# JETSON.net
KiCad netlist of a schematic drawn in Altium Designer
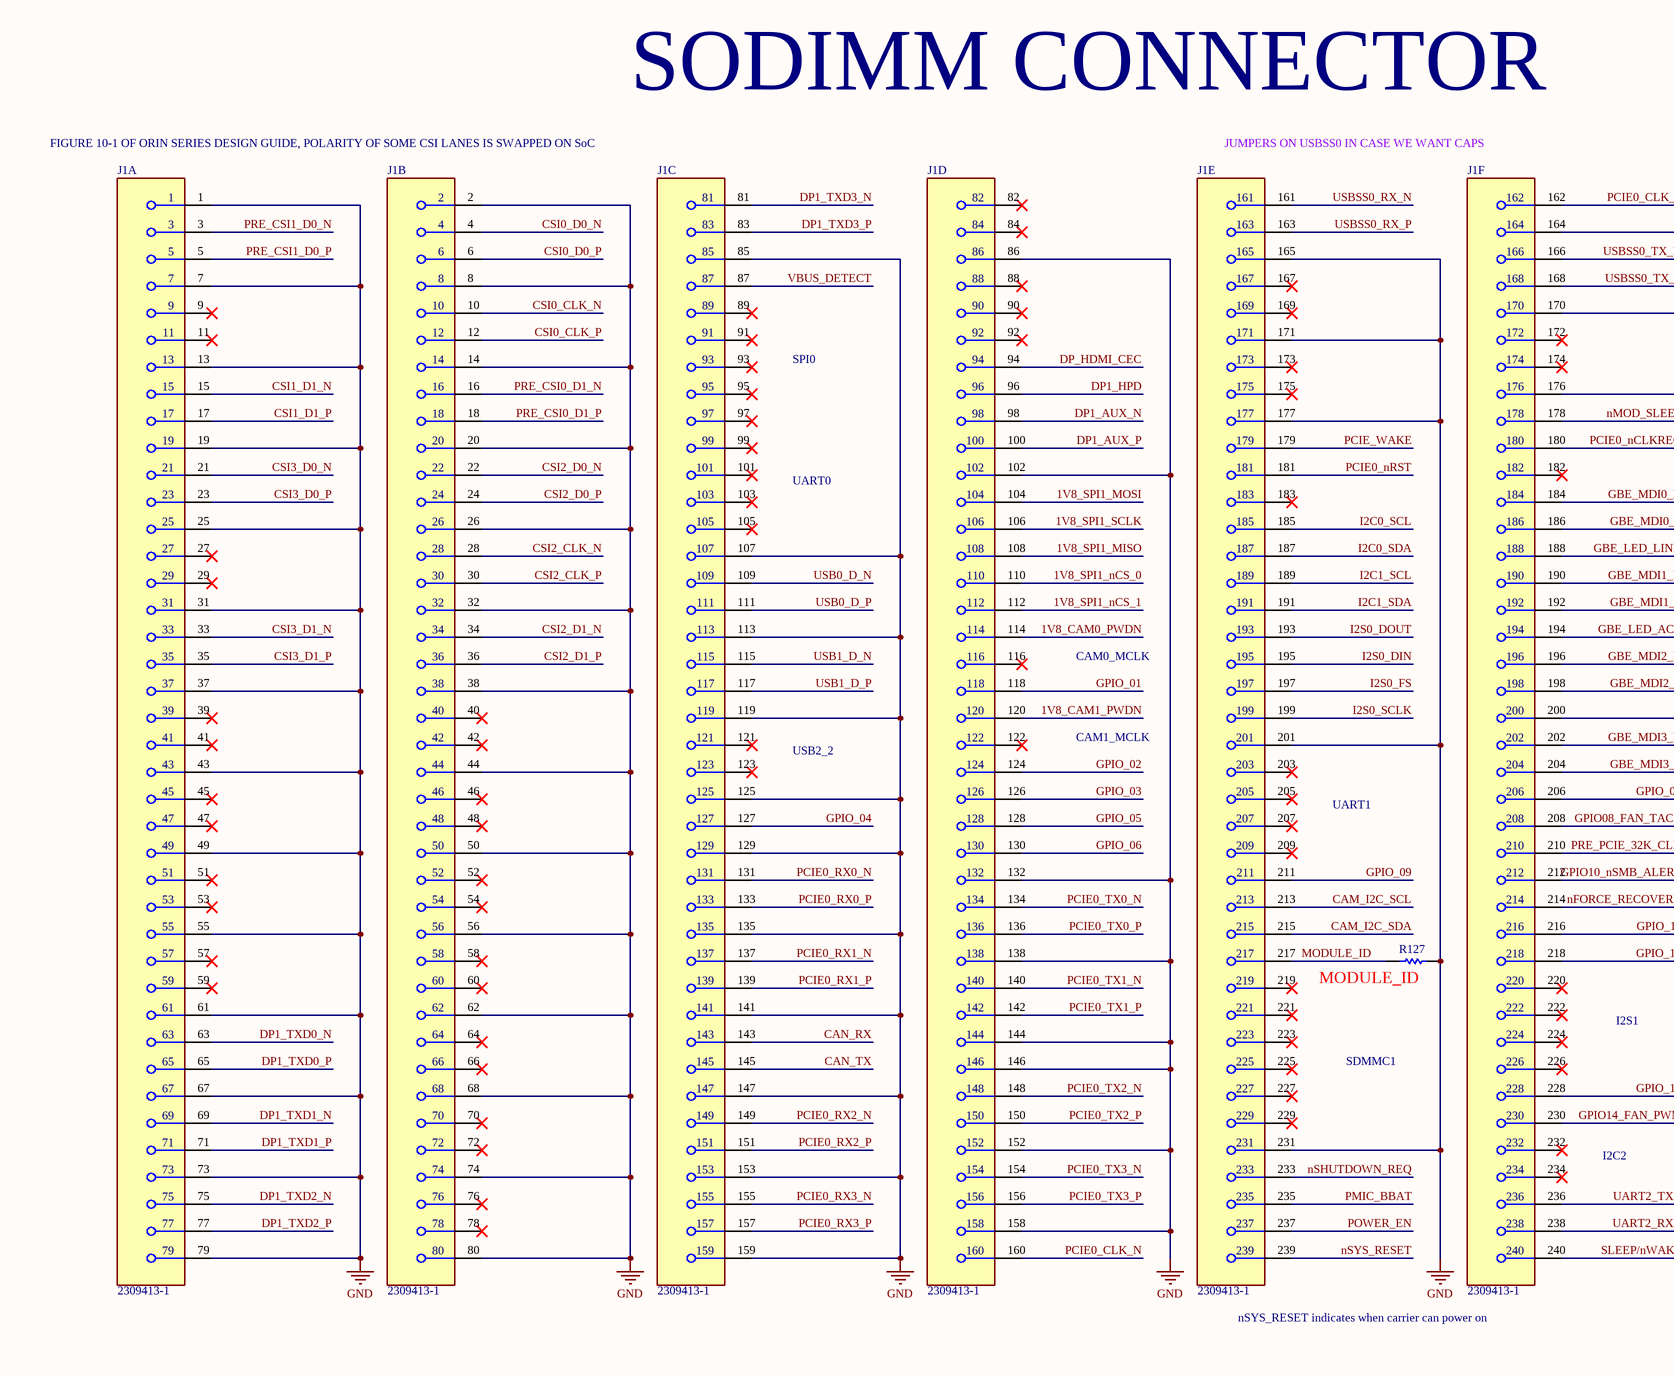
[diagram p0: JETSON.SchDoc, top left]
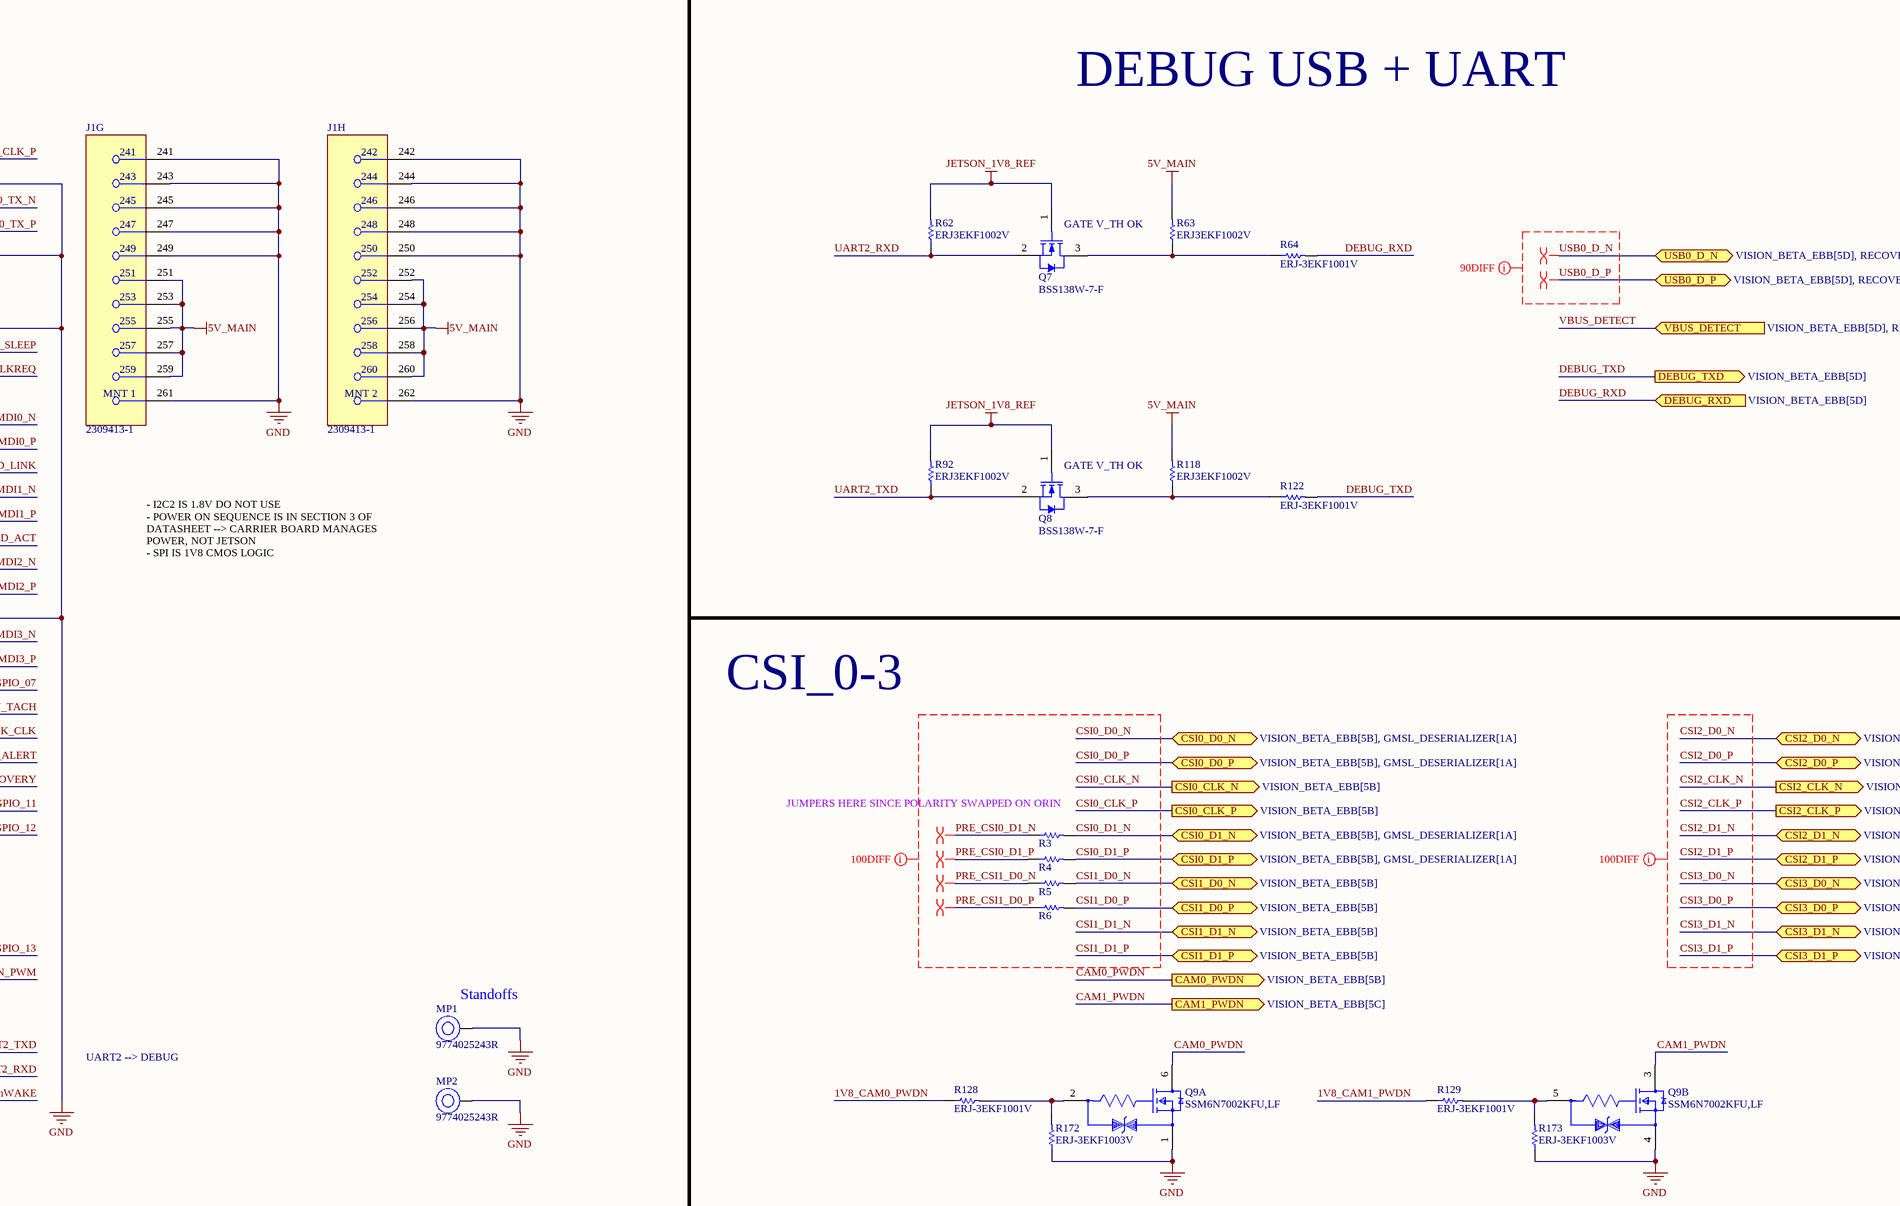
[diagram p1: JETSON.SchDoc, top middle]
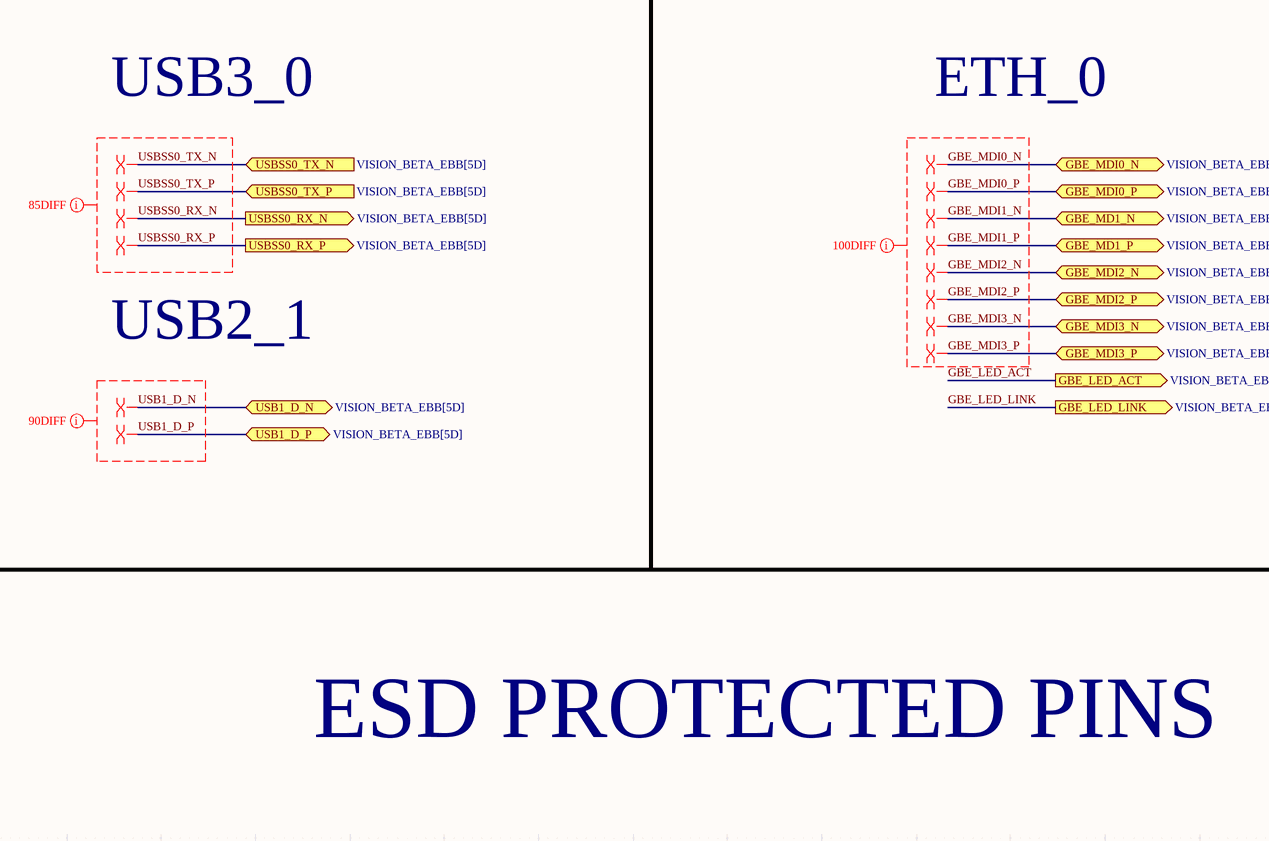
[diagram p2: JETSON.SchDoc, top right]
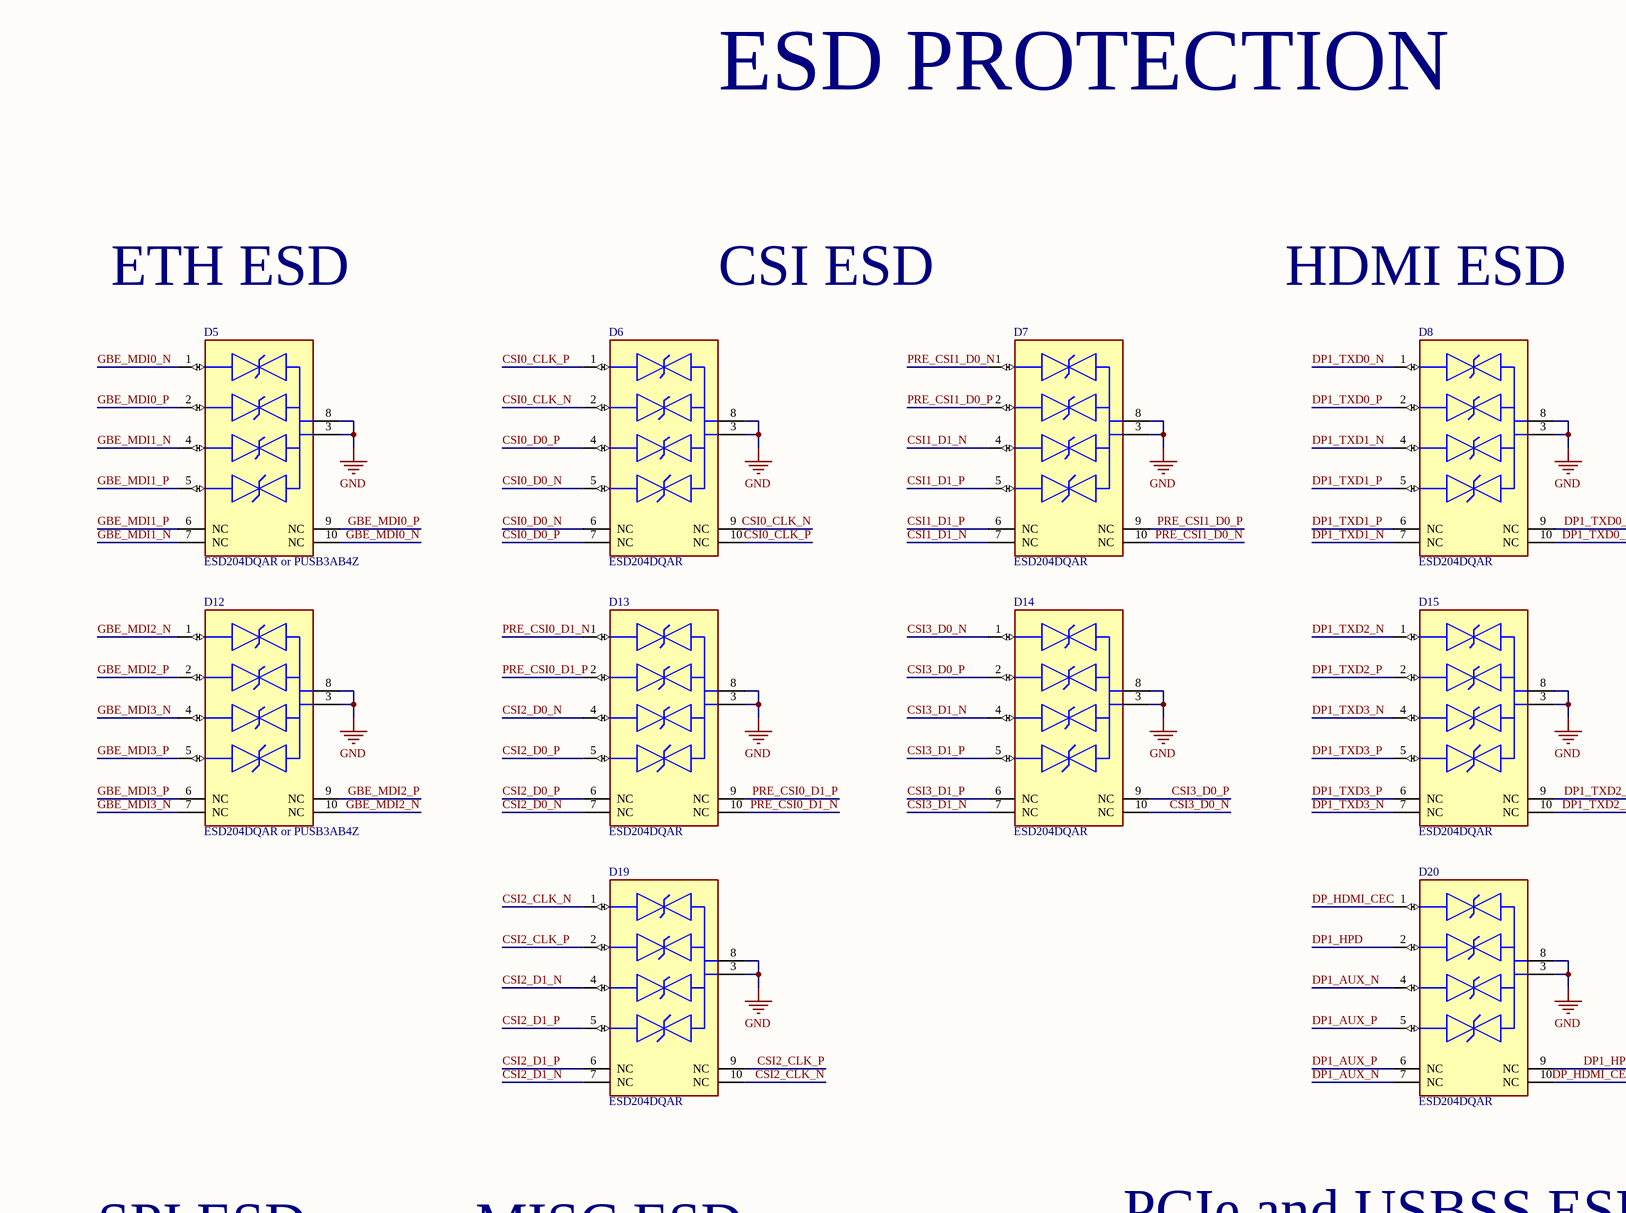
[diagram p3: JETSON.SchDoc, centre left]
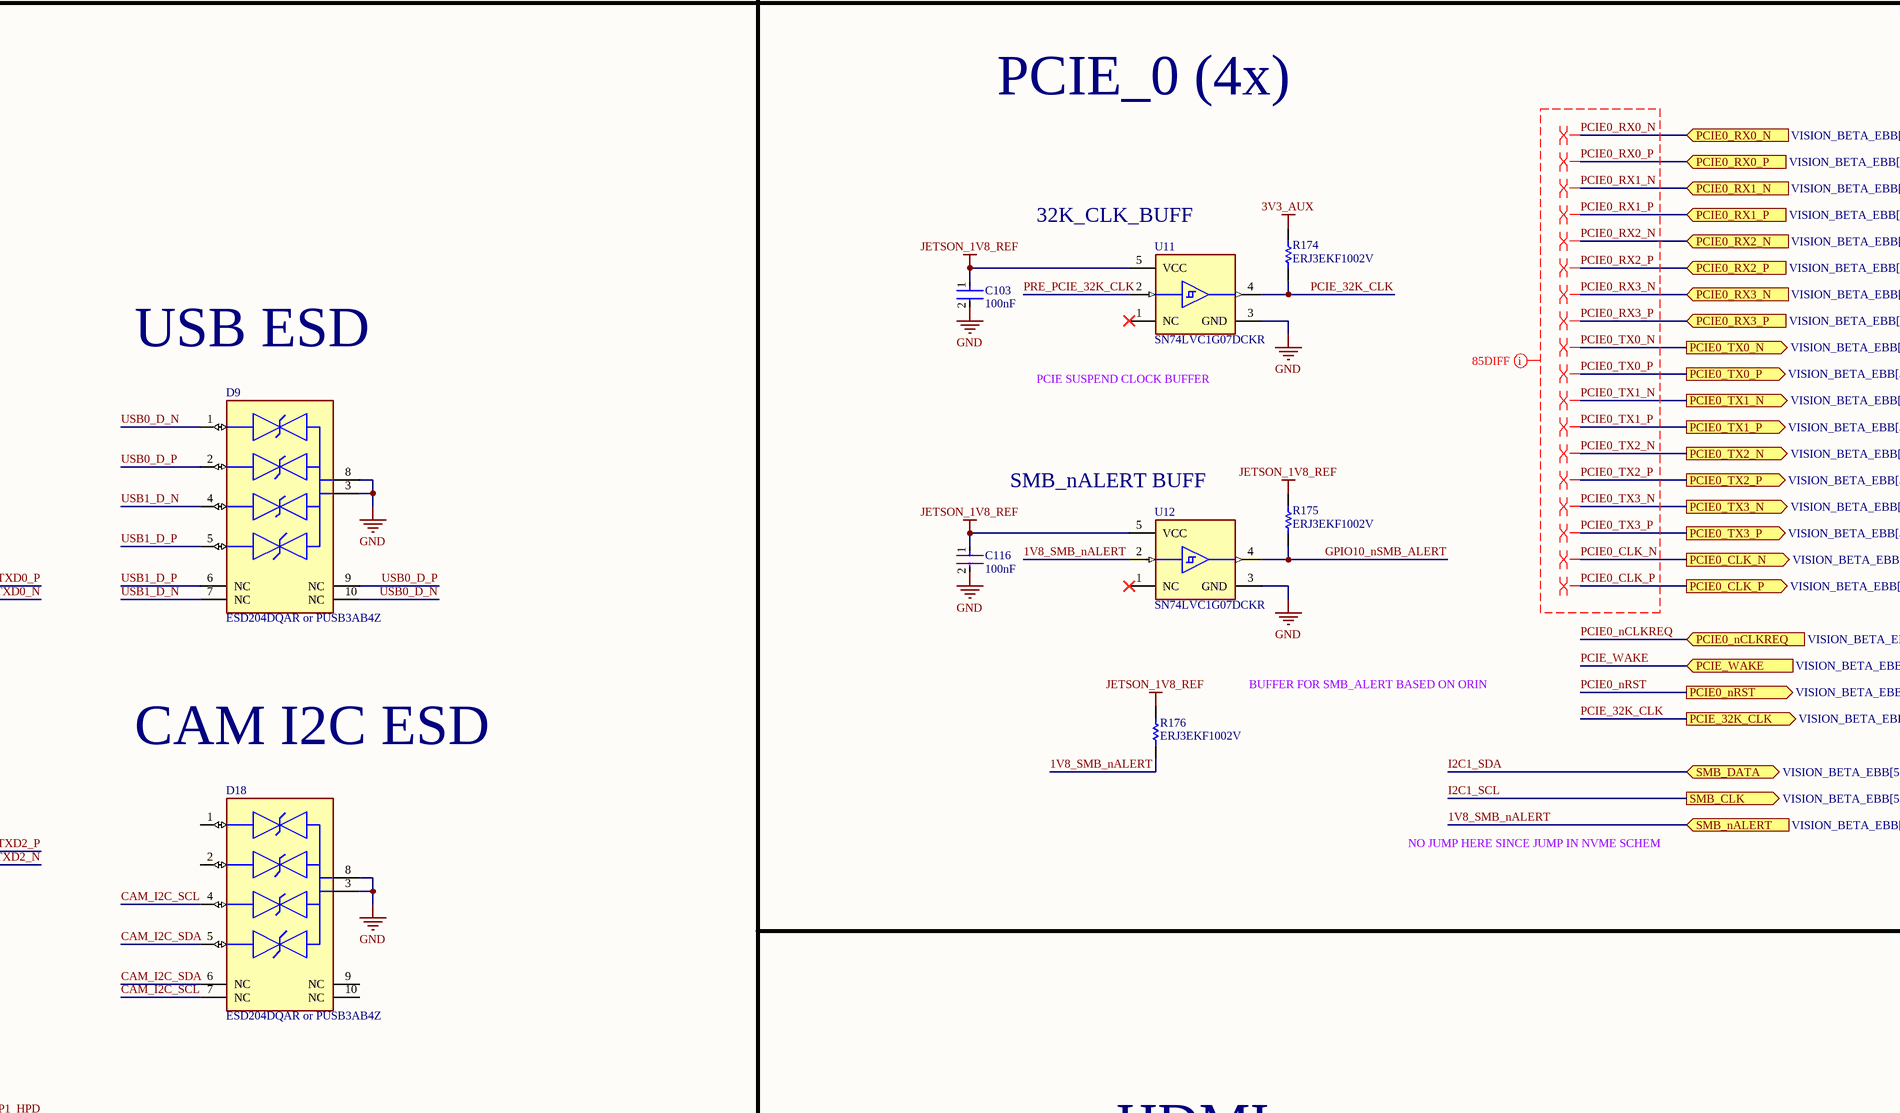
[diagram p4: JETSON.SchDoc, centre middle]
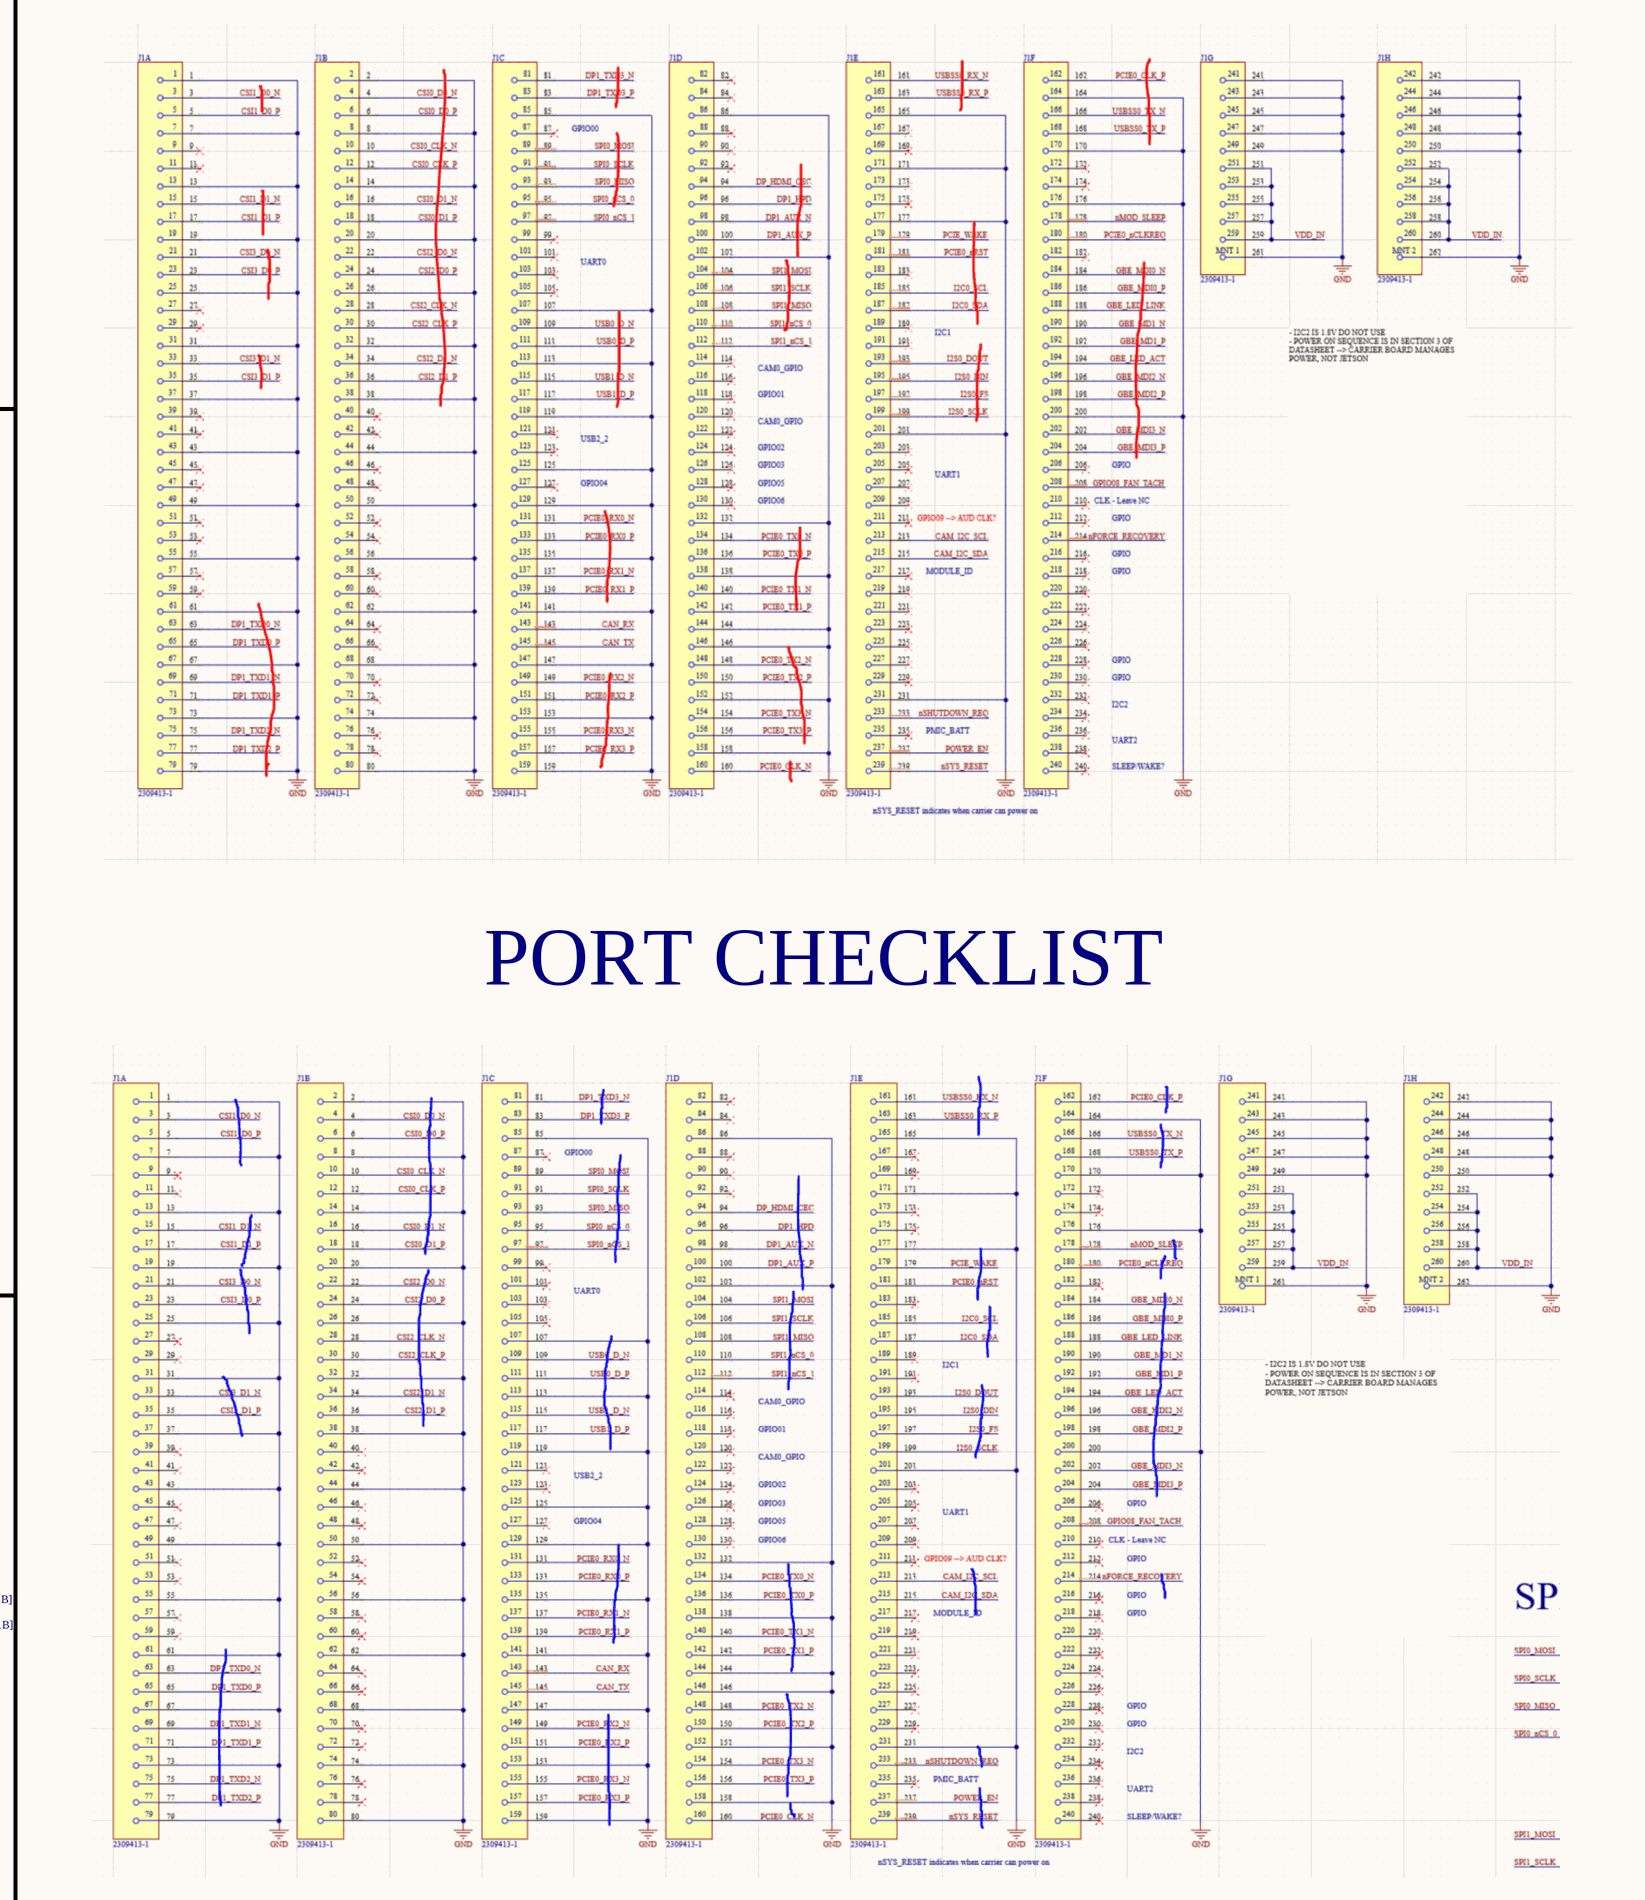
[diagram p5: JETSON.SchDoc, centre right]
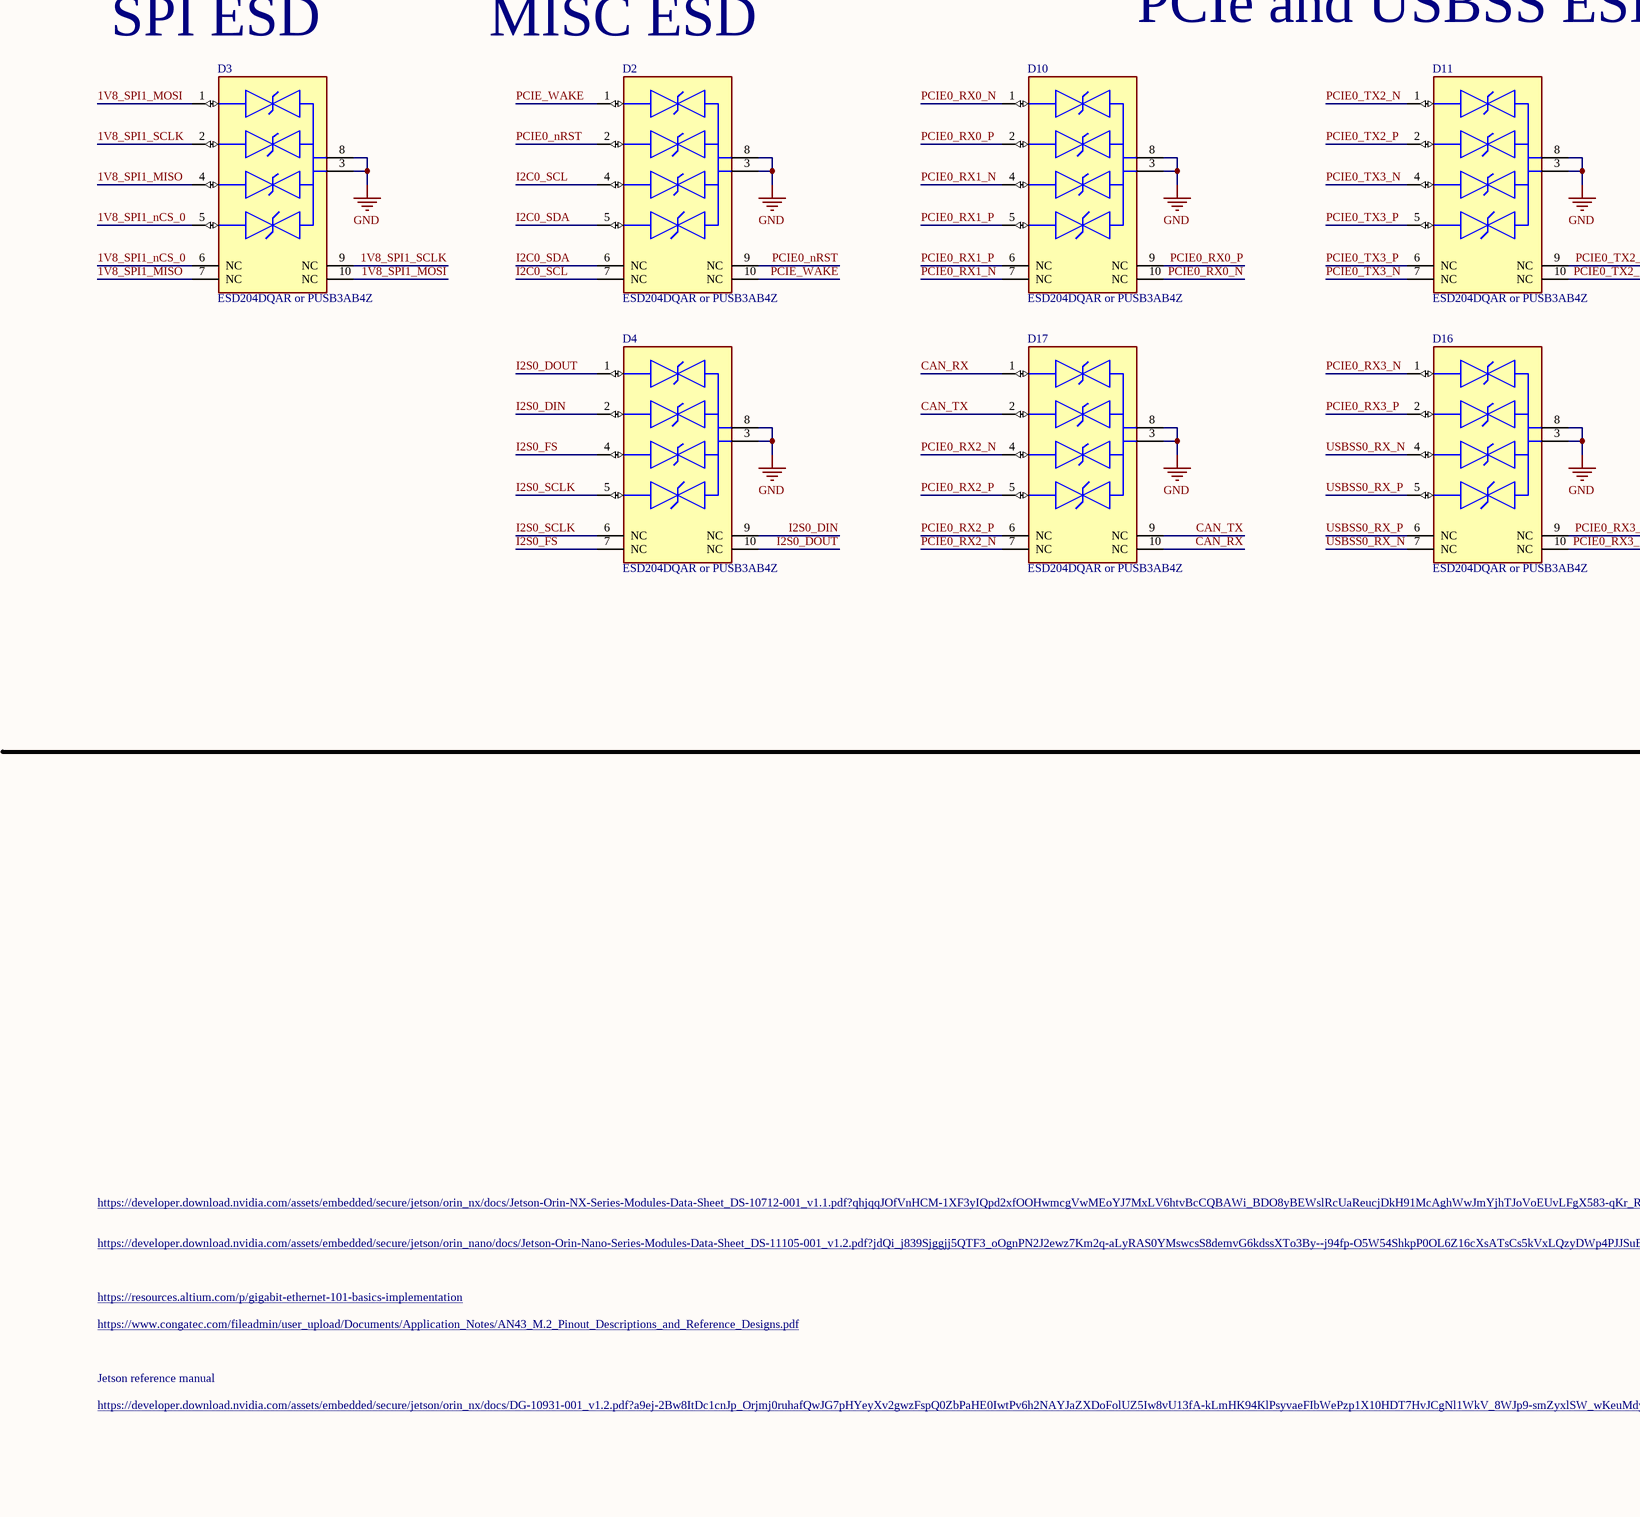
[diagram p6: JETSON.SchDoc, bottom left]
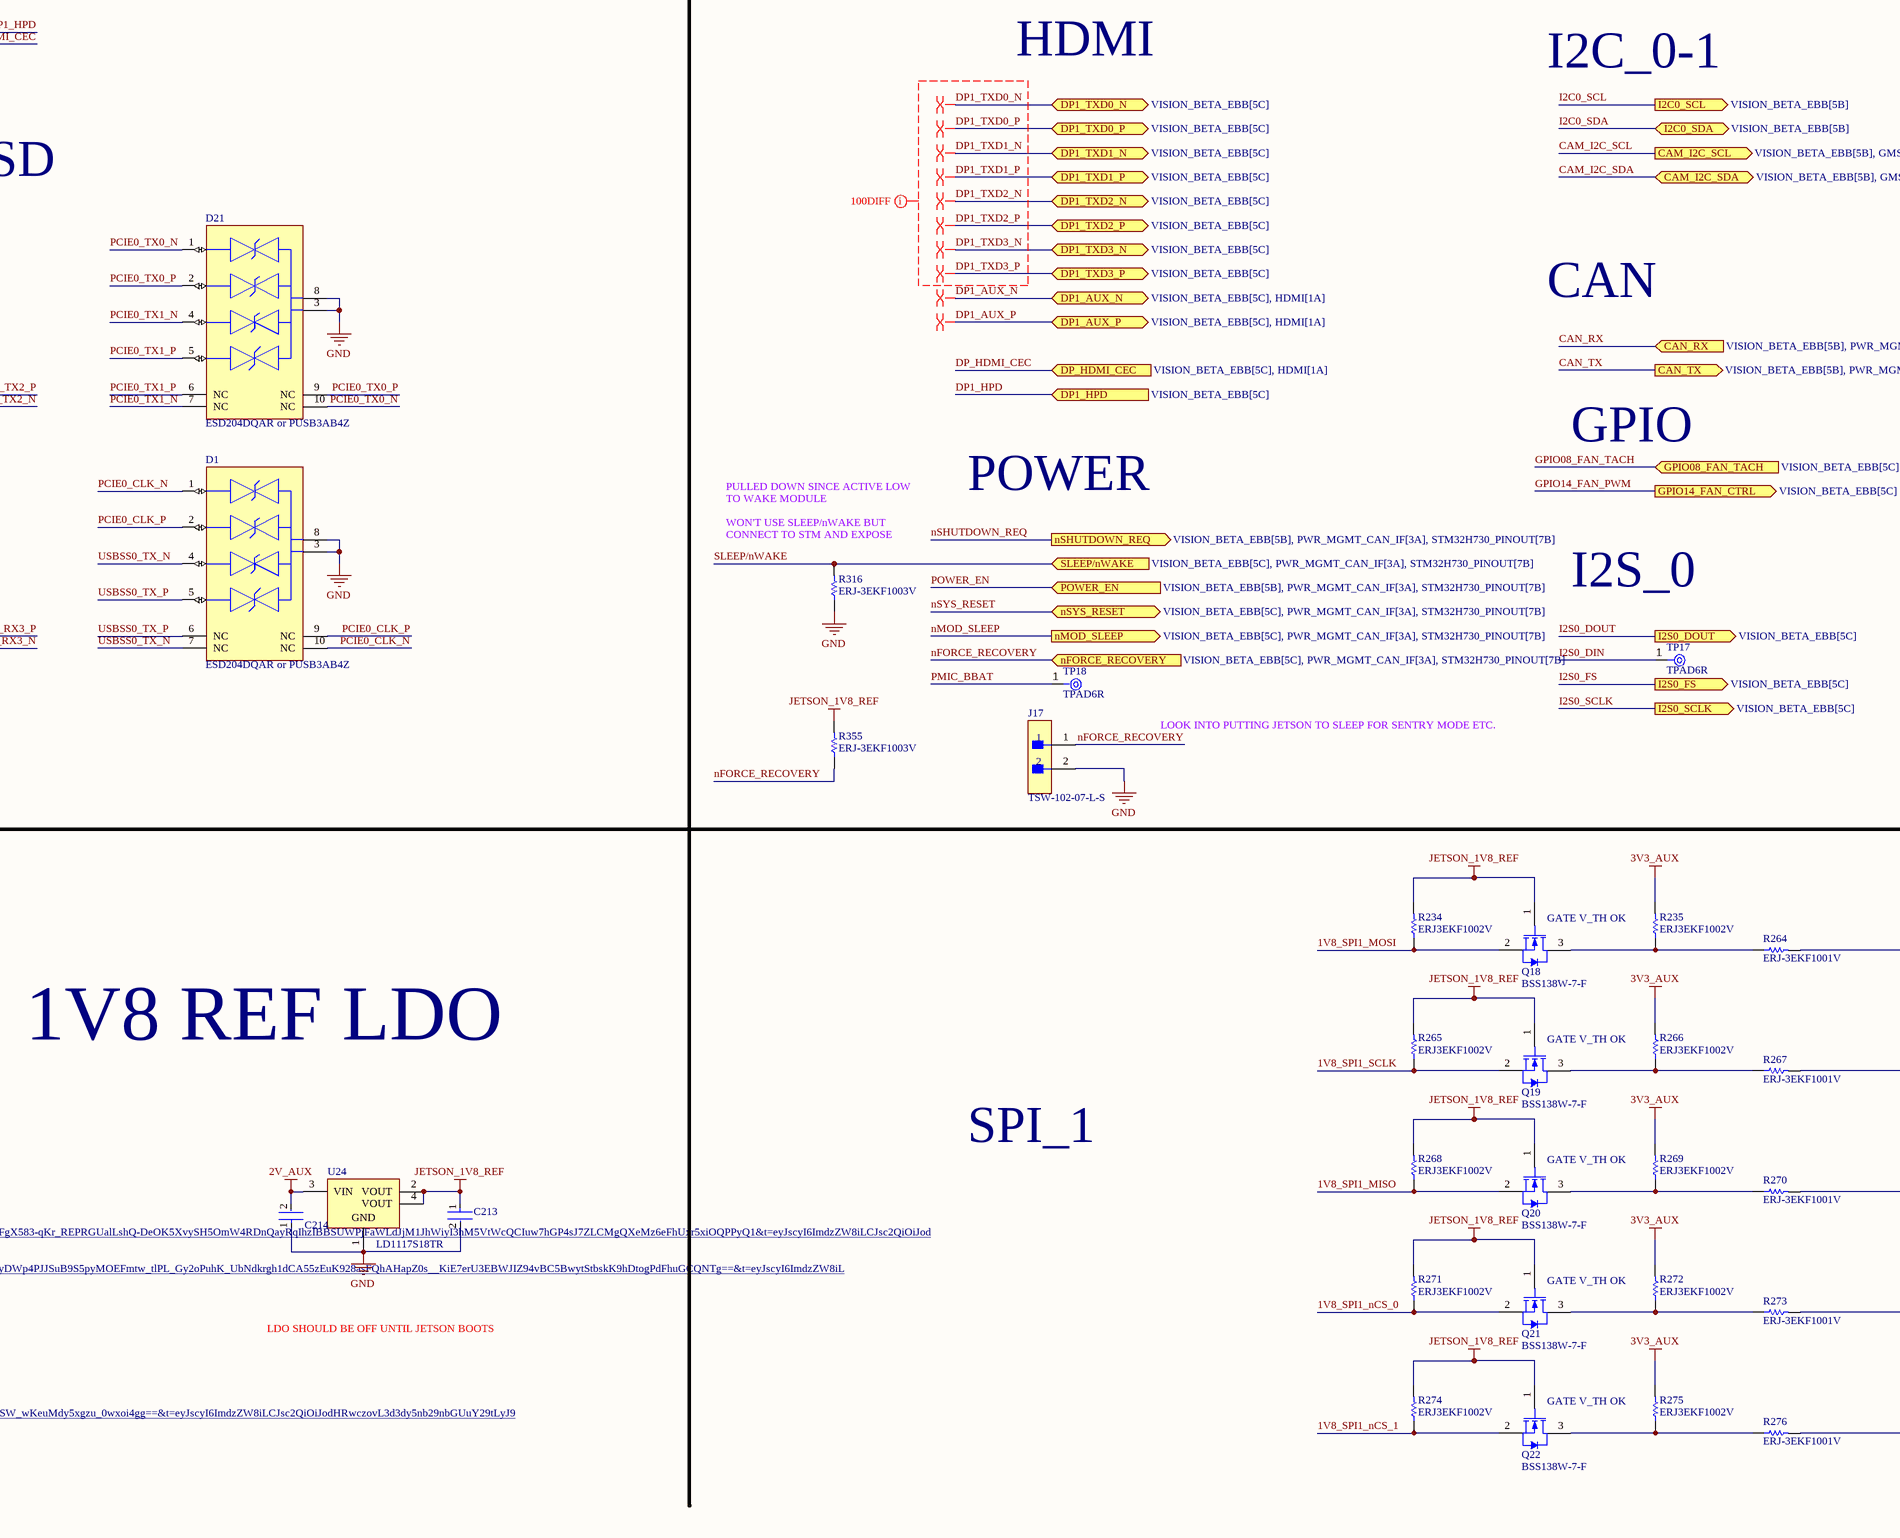
[diagram p7: JETSON.SchDoc, bottom middle]
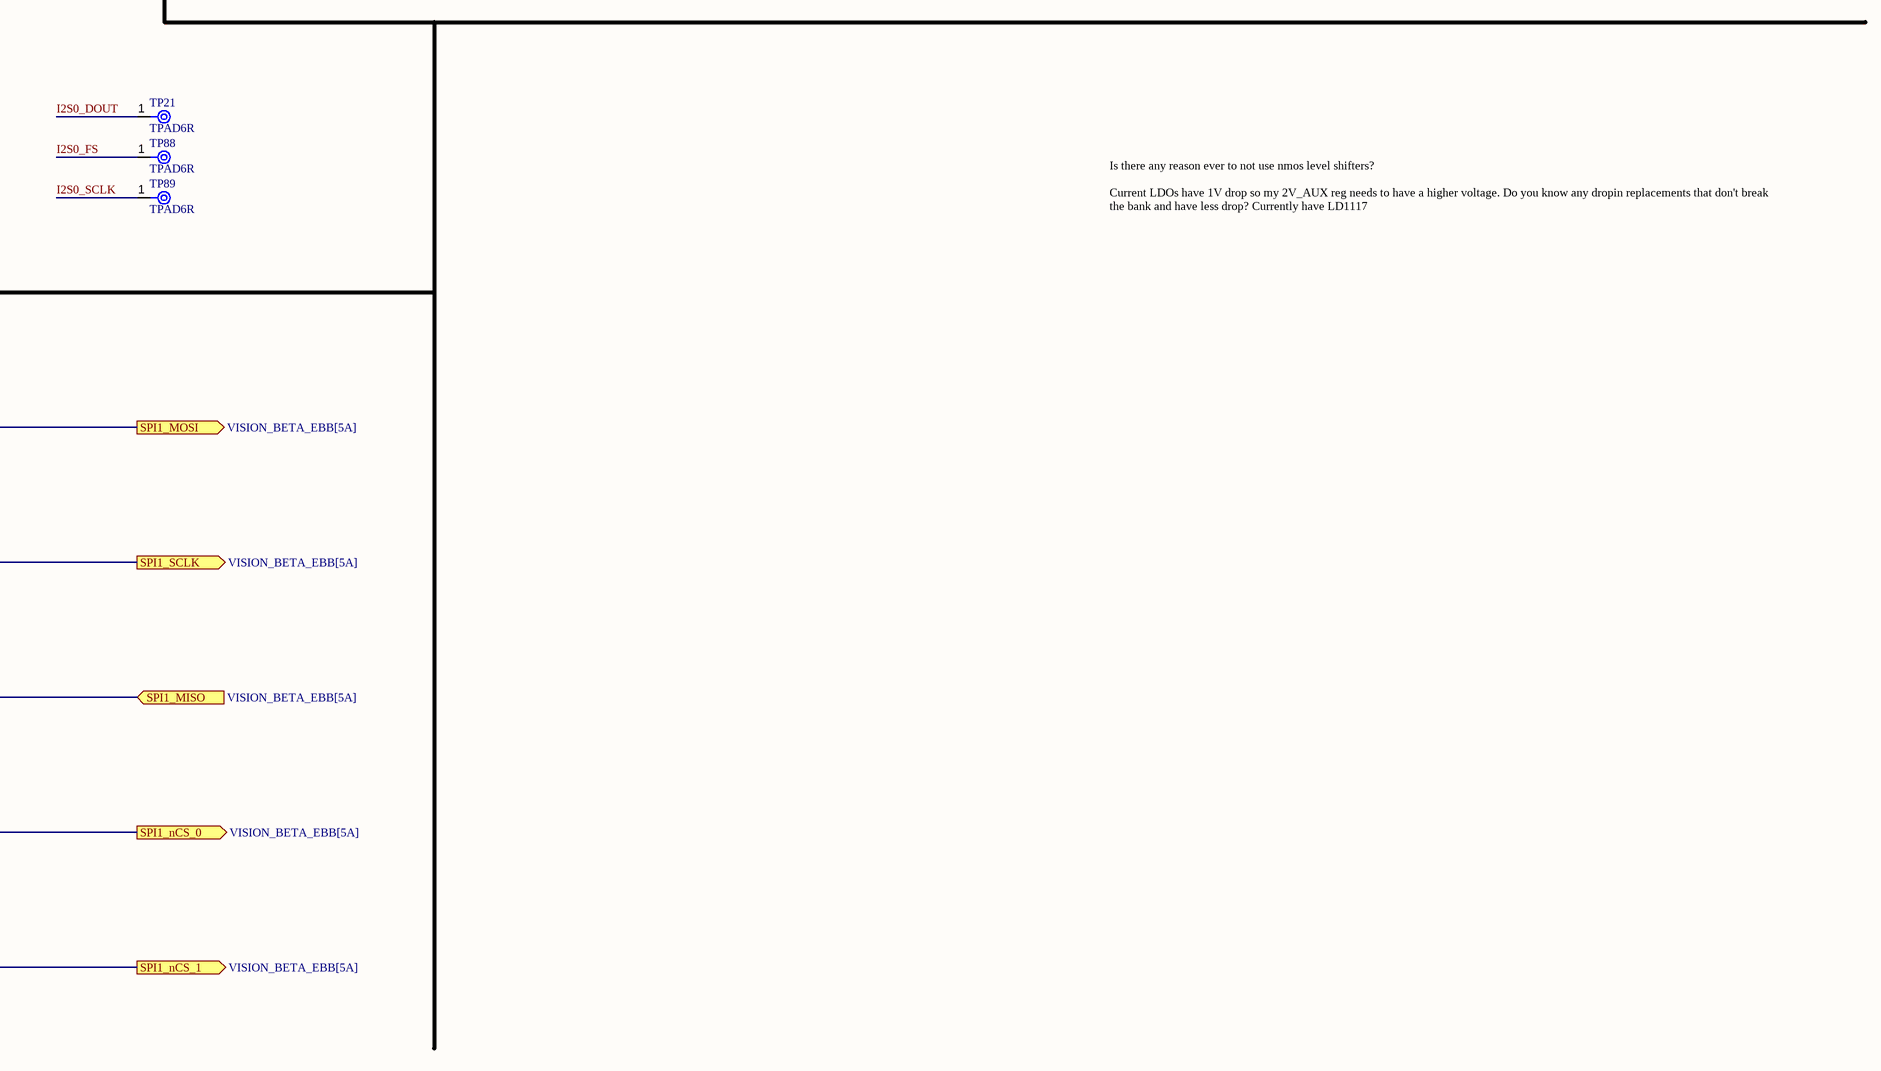
[diagram p8: JETSON.SchDoc, bottom right]

(export (version "E")
  (design (tool "Eeschema 10.0.6"))
  (components
    (comp (ref "C103")
      (value "100nF")
      (footprint "FP-0402-L_1_0_0_05-W_0_5-IPC_A")
      (description "LARGE PADS, 0402 CAP, CHANGE COMMENT TO MATCH REAL P/N")
      (libsource (lib "Space Concordia") (part "b4654b650e69147ec39a6b967a45e02"))
    )
    (comp (ref "C116")
      (value "100nF")
      (footprint "FP-0402-L_1_0_0_05-W_0_5-IPC_A")
      (description "LARGE PADS, 0402 CAP, CHANGE COMMENT TO MATCH REAL P/N")
      (libsource (lib "Space Concordia") (part "b4654b650e69147ec39a6b967a45e02"))
    )
    (comp (ref "C213")
      (value "GRM188R60J106ME47D")
      (footprint "FP-GRM188-0_1-e0_2_0_55-IPC_A")
      (description "Chip Multilayer Ceramic Capacitors for General Purpose, 0603, 10uF, X5R, 15%, 20%, 6.3V")
      (fields (field (name "VOLTAGE") "6.3V") (field (name "TOLERANCE") "20%"))
      (libsource (lib "Altium Content Vault") (part "02cd4be3c70576c341d710602a673aa"))
    )
    (comp (ref "C214")
      (value "C1005X7R1H104K050BB")
      (footprint "FP-C1005-050-0_05-IPC_C")
      (description "Multilayer Ceramic Capacitors 100nF ±10% 50V X7R SMD 0402")
      (fields (field (name "VOLTAGE") "50V") (field (name "TOLERANCE") "10%"))
      (libsource (lib "Altium Content Vault") (part "b4654b650e69147ec39a6b967a45e02"))
    )
    (comp (ref "D1")
      (value "ESD204DQAR or PUSB3AB4Z")
      (footprint "FP-DQA0010A-MFG")
      (description "4-CHANNEL LOW-CAPACITANCE SURGE")
      (fields
        (field (name "MANUFACTURER") "Texas Instruments")
        (field (name "OCTOPART") "https://octopart.com/esd204dqar-texas+instruments-89917476")
      )
      (libsource (lib "Altium Content Vault") (part "1465e58c1818c7767b55926832f0bf5"))
    )
    (comp (ref "D2")
      (value "ESD204DQAR or PUSB3AB4Z")
      (footprint "FP-DQA0010A-MFG")
      (description "4-CHANNEL LOW-CAPACITANCE SURGE")
      (fields
        (field (name "MANUFACTURER") "Texas Instruments")
        (field (name "OCTOPART") "https://octopart.com/esd204dqar-texas+instruments-89917476")
      )
      (libsource (lib "Altium Content Vault") (part "1465e58c1818c7767b55926832f0bf5"))
    )
    (comp (ref "D3")
      (value "ESD204DQAR or PUSB3AB4Z")
      (footprint "FP-DQA0010A-MFG")
      (description "4-CHANNEL LOW-CAPACITANCE SURGE")
      (fields
        (field (name "MANUFACTURER") "Texas Instruments")
        (field (name "OCTOPART") "https://octopart.com/esd204dqar-texas+instruments-89917476")
      )
      (libsource (lib "Altium Content Vault") (part "1465e58c1818c7767b55926832f0bf5"))
    )
    (comp (ref "D4")
      (value "ESD204DQAR or PUSB3AB4Z")
      (footprint "FP-DQA0010A-MFG")
      (description "4-CHANNEL LOW-CAPACITANCE SURGE")
      (fields
        (field (name "MANUFACTURER") "Texas Instruments")
        (field (name "OCTOPART") "https://octopart.com/esd204dqar-texas+instruments-89917476")
      )
      (libsource (lib "Altium Content Vault") (part "1465e58c1818c7767b55926832f0bf5"))
    )
    (comp (ref "D5")
      (value "ESD204DQAR or PUSB3AB4Z")
      (footprint "FP-DQA0010A-MFG")
      (description "4-CHANNEL LOW-CAPACITANCE SURGE")
      (fields
        (field (name "MANUFACTURER") "Texas Instruments")
        (field (name "OCTOPART") "https://octopart.com/esd204dqar-texas+instruments-89917476")
      )
      (libsource (lib "Altium Content Vault") (part "1465e58c1818c7767b55926832f0bf5"))
    )
    (comp (ref "D6")
      (value "ESD204DQAR")
      (footprint "FP-DQA0010A-MFG")
      (description "4-CHANNEL LOW-CAPACITANCE SURGE")
      (fields
        (field (name "MANUFACTURER") "Texas Instruments")
        (field (name "OCTOPART") "https://octopart.com/esd204dqar-texas+instruments-89917476")
      )
      (libsource (lib "Altium Content Vault") (part "1465e58c1818c7767b55926832f0bf5"))
    )
    (comp (ref "D7")
      (value "ESD204DQAR")
      (footprint "FP-DQA0010A-MFG")
      (description "4-CHANNEL LOW-CAPACITANCE SURGE")
      (fields
        (field (name "MANUFACTURER") "Texas Instruments")
        (field (name "OCTOPART") "https://octopart.com/esd204dqar-texas+instruments-89917476")
      )
      (libsource (lib "Altium Content Vault") (part "1465e58c1818c7767b55926832f0bf5"))
    )
    (comp (ref "D8")
      (value "ESD204DQAR")
      (footprint "FP-DQA0010A-MFG")
      (description "4-CHANNEL LOW-CAPACITANCE SURGE")
      (fields
        (field (name "MANUFACTURER") "Texas Instruments")
        (field (name "OCTOPART") "https://octopart.com/esd204dqar-texas+instruments-89917476")
      )
      (libsource (lib "Altium Content Vault") (part "1465e58c1818c7767b55926832f0bf5"))
    )
    (comp (ref "D9")
      (value "ESD204DQAR or PUSB3AB4Z")
      (footprint "FP-DQA0010A-MFG")
      (description "4-CHANNEL LOW-CAPACITANCE SURGE")
      (fields
        (field (name "MANUFACTURER") "Texas Instruments")
        (field (name "OCTOPART") "https://octopart.com/esd204dqar-texas+instruments-89917476")
      )
      (libsource (lib "Altium Content Vault") (part "1465e58c1818c7767b55926832f0bf5"))
    )
    (comp (ref "D10")
      (value "ESD204DQAR or PUSB3AB4Z")
      (footprint "FP-DQA0010A-MFG")
      (description "4-CHANNEL LOW-CAPACITANCE SURGE")
      (fields
        (field (name "MANUFACTURER") "Texas Instruments")
        (field (name "OCTOPART") "https://octopart.com/esd204dqar-texas+instruments-89917476")
      )
      (libsource (lib "Altium Content Vault") (part "1465e58c1818c7767b55926832f0bf5"))
    )
    (comp (ref "D11")
      (value "ESD204DQAR or PUSB3AB4Z")
      (footprint "FP-DQA0010A-MFG")
      (description "4-CHANNEL LOW-CAPACITANCE SURGE")
      (fields
        (field (name "MANUFACTURER") "Texas Instruments")
        (field (name "OCTOPART") "https://octopart.com/esd204dqar-texas+instruments-89917476")
      )
      (libsource (lib "Altium Content Vault") (part "1465e58c1818c7767b55926832f0bf5"))
    )
    (comp (ref "D12")
      (value "ESD204DQAR or PUSB3AB4Z")
      (footprint "FP-DQA0010A-MFG")
      (description "4-CHANNEL LOW-CAPACITANCE SURGE")
      (fields
        (field (name "MANUFACTURER") "Texas Instruments")
        (field (name "OCTOPART") "https://octopart.com/esd204dqar-texas+instruments-89917476")
      )
      (libsource (lib "Altium Content Vault") (part "1465e58c1818c7767b55926832f0bf5"))
    )
    (comp (ref "D13")
      (value "ESD204DQAR")
      (footprint "FP-DQA0010A-MFG")
      (description "4-CHANNEL LOW-CAPACITANCE SURGE")
      (fields
        (field (name "MANUFACTURER") "Texas Instruments")
        (field (name "OCTOPART") "https://octopart.com/esd204dqar-texas+instruments-89917476")
      )
      (libsource (lib "Altium Content Vault") (part "1465e58c1818c7767b55926832f0bf5"))
    )
    (comp (ref "D14")
      (value "ESD204DQAR")
      (footprint "FP-DQA0010A-MFG")
      (description "4-CHANNEL LOW-CAPACITANCE SURGE")
      (fields
        (field (name "MANUFACTURER") "Texas Instruments")
        (field (name "OCTOPART") "https://octopart.com/esd204dqar-texas+instruments-89917476")
      )
      (libsource (lib "Altium Content Vault") (part "1465e58c1818c7767b55926832f0bf5"))
    )
    (comp (ref "D15")
      (value "ESD204DQAR")
      (footprint "FP-DQA0010A-MFG")
      (description "4-CHANNEL LOW-CAPACITANCE SURGE")
      (fields
        (field (name "MANUFACTURER") "Texas Instruments")
        (field (name "OCTOPART") "https://octopart.com/esd204dqar-texas+instruments-89917476")
      )
      (libsource (lib "Altium Content Vault") (part "1465e58c1818c7767b55926832f0bf5"))
    )
    (comp (ref "D16")
      (value "ESD204DQAR or PUSB3AB4Z")
      (footprint "FP-DQA0010A-MFG")
      (description "4-CHANNEL LOW-CAPACITANCE SURGE")
      (fields
        (field (name "MANUFACTURER") "Texas Instruments")
        (field (name "OCTOPART") "https://octopart.com/esd204dqar-texas+instruments-89917476")
      )
      (libsource (lib "Altium Content Vault") (part "1465e58c1818c7767b55926832f0bf5"))
    )
    (comp (ref "D17")
      (value "ESD204DQAR or PUSB3AB4Z")
      (footprint "FP-DQA0010A-MFG")
      (description "4-CHANNEL LOW-CAPACITANCE SURGE")
      (fields
        (field (name "MANUFACTURER") "Texas Instruments")
        (field (name "OCTOPART") "https://octopart.com/esd204dqar-texas+instruments-89917476")
      )
      (libsource (lib "Altium Content Vault") (part "1465e58c1818c7767b55926832f0bf5"))
    )
    (comp (ref "D18")
      (value "ESD204DQAR or PUSB3AB4Z")
      (footprint "FP-DQA0010A-MFG")
      (description "4-CHANNEL LOW-CAPACITANCE SURGE")
      (fields
        (field (name "MANUFACTURER") "Texas Instruments")
        (field (name "OCTOPART") "https://octopart.com/esd204dqar-texas+instruments-89917476")
      )
      (libsource (lib "Altium Content Vault") (part "1465e58c1818c7767b55926832f0bf5"))
    )
    (comp (ref "D19")
      (value "ESD204DQAR")
      (footprint "FP-DQA0010A-MFG")
      (description "4-CHANNEL LOW-CAPACITANCE SURGE")
      (fields
        (field (name "MANUFACTURER") "Texas Instruments")
        (field (name "OCTOPART") "https://octopart.com/esd204dqar-texas+instruments-89917476")
      )
      (libsource (lib "Altium Content Vault") (part "1465e58c1818c7767b55926832f0bf5"))
    )
    (comp (ref "D20")
      (value "ESD204DQAR")
      (footprint "FP-DQA0010A-MFG")
      (description "4-CHANNEL LOW-CAPACITANCE SURGE")
      (fields
        (field (name "MANUFACTURER") "Texas Instruments")
        (field (name "OCTOPART") "https://octopart.com/esd204dqar-texas+instruments-89917476")
      )
      (libsource (lib "Altium Content Vault") (part "1465e58c1818c7767b55926832f0bf5"))
    )
    (comp (ref "D21")
      (value "ESD204DQAR or PUSB3AB4Z")
      (footprint "FP-DQA0010A-MFG")
      (description "4-CHANNEL LOW-CAPACITANCE SURGE")
      (fields
        (field (name "MANUFACTURER") "Texas Instruments")
        (field (name "OCTOPART") "https://octopart.com/esd204dqar-texas+instruments-89917476")
      )
      (libsource (lib "Altium Content Vault") (part "1465e58c1818c7767b55926832f0bf5"))
    )
    (comp (ref "J1")
      (value "2309413-1")
      (footprint "FP-2309413-1-MFG")
      (description "DDR4 SODIMM 260P 9.2H STD")
      (fields
        (field (name "OCTOPART") "https://octopart.com/2309413-1-te+connectivity-84799194")
        (field (name "MANUFACTURER") "TE Connectivity")
      )
      (libsource (lib "Altium Content Vault") (part "4d1075b24ee2591bdcd47d674b3d2aa"))
    )
    (comp (ref "J17")
      (value "TSW-102-07-L-S")
      (footprint "FP-TSW-102-07-L-S-MFG")
      (description "CONN HEADER VERT 2POS 2.54MM")
      (libsource (lib "Altium Content Vault") (part "3bc925449376181038e59eaffc5286c"))
    )
    (comp (ref "MP1")
      (value "9774025243R")
      (footprint "9774025243")
      (description "9774025243R Spacer Material: Steel, Tin-Plated Mounting: SMT Series: WA-SMST Thread D: M2")
      (libsource (lib "Altium Content Vault") (part "Spacer"))
    )
    (comp (ref "MP2")
      (value "9774025243R")
      (footprint "9774025243")
      (description "9774025243R Spacer Material: Steel, Tin-Plated Mounting: SMT Series: WA-SMST Thread D: M2")
      (libsource (lib "Altium Content Vault") (part "Spacer"))
    )
    (comp (ref "Q7")
      (value "BSS138W-7-F")
      (footprint "DIOD-SOT323-3_V")
      (fields (field (name "MANUFACTURER") "DiodesIncorporated"))
      (libsource (lib "Altium Content Vault") (part "NEMOS-GSD-3"))
    )
    (comp (ref "Q8")
      (value "BSS138W-7-F")
      (footprint "DIOD-SOT323-3_V")
      (fields (field (name "MANUFACTURER") "DiodesIncorporated"))
      (libsource (lib "Altium Content Vault") (part "NEMOS-GSD-3"))
    )
    (comp (ref "Q9")
      (value "SSM6N7002KFU,LF")
      (footprint "FP-SSOP6-P-0_65A-MFG")
      (description "MOSFET 2N-CH 60V 0.3A")
      (libsource (lib "Altium Content Vault") (part "088aa6ac103fdeebe0d1c52ece6b7b9"))
    )
    (comp (ref "Q18")
      (value "BSS138W-7-F")
      (footprint "DIOD-SOT323-3_V")
      (fields (field (name "MANUFACTURER") "DiodesIncorporated"))
      (libsource (lib "Altium Content Vault") (part "NEMOS-GSD-3"))
    )
    (comp (ref "Q19")
      (value "BSS138W-7-F")
      (footprint "DIOD-SOT323-3_V")
      (fields (field (name "MANUFACTURER") "DiodesIncorporated"))
      (libsource (lib "Altium Content Vault") (part "NEMOS-GSD-3"))
    )
    (comp (ref "Q20")
      (value "BSS138W-7-F")
      (footprint "DIOD-SOT323-3_V")
      (fields (field (name "MANUFACTURER") "DiodesIncorporated"))
      (libsource (lib "Altium Content Vault") (part "NEMOS-GSD-3"))
    )
    (comp (ref "Q21")
      (value "BSS138W-7-F")
      (footprint "DIOD-SOT323-3_V")
      (fields (field (name "MANUFACTURER") "DiodesIncorporated"))
      (libsource (lib "Altium Content Vault") (part "NEMOS-GSD-3"))
    )
    (comp (ref "Q22")
      (value "BSS138W-7-F")
      (footprint "DIOD-SOT323-3_V")
      (fields (field (name "MANUFACTURER") "DiodesIncorporated"))
      (libsource (lib "Altium Content Vault") (part "NEMOS-GSD-3"))
    )
    (comp (ref "R3")
      (value "0402 JUMPER")
      (footprint "RESC1005X40X25ML05T05")
      (description "READ THE NAME")
      (libsource (lib "Space Concordia") (part "CMP-009-00206-2"))
    )
    (comp (ref "R4")
      (value "0402 JUMPER")
      (footprint "RESC1005X40X25ML05T05")
      (description "READ THE NAME")
      (libsource (lib "Space Concordia") (part "CMP-009-00206-2"))
    )
    (comp (ref "R5")
      (value "0402 JUMPER")
      (footprint "RESC1005X40X25ML05T05")
      (description "READ THE NAME")
      (libsource (lib "Space Concordia") (part "CMP-009-00206-2"))
    )
    (comp (ref "R6")
      (value "0402 JUMPER")
      (footprint "RESC1005X40X25ML05T05")
      (description "READ THE NAME")
      (libsource (lib "Space Concordia") (part "CMP-009-00206-2"))
    )
    (comp (ref "R62")
      (value "ERJ3EKF1002V")
      (footprint "RESC1609X55X30LL15T15")
      (description "Chip Resistor, 10 KOhm, +/- 1%, 0.1 W, -55 to 155 degC, 0603 (1608 Metric), RoHS, Tape and Reel")
      (fields (field (name "TOLERANCE") "1%") (field (name "MANUFACTURER") "Panasonic"))
      (libsource (lib "Altium Content Vault") (part "RES-2"))
    )
    (comp (ref "R63")
      (value "ERJ3EKF1002V")
      (footprint "RESC1609X55X30LL15T15")
      (description "Chip Resistor, 10 KOhm, +/- 1%, 0.1 W, -55 to 155 degC, 0603 (1608 Metric), RoHS, Tape and Reel")
      (fields (field (name "TOLERANCE") "1%") (field (name "MANUFACTURER") "Panasonic"))
      (libsource (lib "Altium Content Vault") (part "RES-2"))
    )
    (comp (ref "R64")
      (value "ERJ-3EKF1001V")
      (footprint "RESC1608X55X30LL15T15")
      (fields (field (name "MANUFACTURER") "Panasonic"))
      (libsource (lib "Altium Content Vault") (part "RES"))
    )
    (comp (ref "R92")
      (value "ERJ3EKF1002V")
      (footprint "RESC1609X55X30LL15T15")
      (description "Chip Resistor, 10 KOhm, +/- 1%, 0.1 W, -55 to 155 degC, 0603 (1608 Metric), RoHS, Tape and Reel")
      (fields (field (name "TOLERANCE") "1%") (field (name "MANUFACTURER") "Panasonic"))
      (libsource (lib "Altium Content Vault") (part "RES-2"))
    )
    (comp (ref "R118")
      (value "ERJ3EKF1002V")
      (footprint "RESC1609X55X30LL15T15")
      (description "Chip Resistor, 10 KOhm, +/- 1%, 0.1 W, -55 to 155 degC, 0603 (1608 Metric), RoHS, Tape and Reel")
      (fields (field (name "TOLERANCE") "1%") (field (name "MANUFACTURER") "Panasonic"))
      (libsource (lib "Altium Content Vault") (part "RES-2"))
    )
    (comp (ref "R122")
      (value "ERJ-3EKF1001V")
      (footprint "RESC1608X55X30LL15T15")
      (fields (field (name "MANUFACTURER") "Panasonic"))
      (libsource (lib "Altium Content Vault") (part "RES"))
    )
    (comp (ref "R127")
      (value "0402 JUMPER")
      (footprint "RESC1005X40X25ML05T05")
      (description "READ THE NAME")
      (libsource (lib "Space Concordia") (part "CMP-009-00206-2"))
    )
    (comp (ref "R128")
      (value "ERJ-3EKF1001V")
      (footprint "RESC1608X55X30LL15T15")
      (fields (field (name "MANUFACTURER") "Panasonic"))
      (libsource (lib "Altium Content Vault") (part "RES"))
    )
    (comp (ref "R129")
      (value "ERJ-3EKF1001V")
      (footprint "RESC1608X55X30LL15T15")
      (fields (field (name "MANUFACTURER") "Panasonic"))
      (libsource (lib "Altium Content Vault") (part "RES"))
    )
    (comp (ref "R172")
      (value "ERJ-3EKF1003V")
      (footprint "RESC1608X55X30ML15T15")
      (fields (field (name "MANUFACTURER") "Panasonic"))
      (libsource (lib "Altium Content Vault") (part "RES"))
    )
    (comp (ref "R173")
      (value "ERJ-3EKF1003V")
      (footprint "RESC1608X55X30ML15T15")
      (fields (field (name "MANUFACTURER") "Panasonic"))
      (libsource (lib "Altium Content Vault") (part "RES"))
    )
    (comp (ref "R174")
      (value "ERJ3EKF1002V")
      (footprint "RESC1609X55X30LL15T15")
      (description "Chip Resistor, 10 KOhm, +/- 1%, 0.1 W, -55 to 155 degC, 0603 (1608 Metric), RoHS, Tape and Reel")
      (fields (field (name "TOLERANCE") "1%") (field (name "MANUFACTURER") "Panasonic"))
      (libsource (lib "Altium Content Vault") (part "RES-2"))
    )
    (comp (ref "R175")
      (value "ERJ3EKF1002V")
      (footprint "RESC1609X55X30LL15T15")
      (description "Chip Resistor, 10 KOhm, +/- 1%, 0.1 W, -55 to 155 degC, 0603 (1608 Metric), RoHS, Tape and Reel")
      (fields (field (name "TOLERANCE") "1%") (field (name "MANUFACTURER") "Panasonic"))
      (libsource (lib "Altium Content Vault") (part "RES-2"))
    )
    (comp (ref "R176")
      (value "ERJ3EKF1002V")
      (footprint "RESC1609X55X30LL15T15")
      (description "Chip Resistor, 10 KOhm, +/- 1%, 0.1 W, -55 to 155 degC, 0603 (1608 Metric), RoHS, Tape and Reel")
      (fields (field (name "TOLERANCE") "1%") (field (name "MANUFACTURER") "Panasonic"))
      (libsource (lib "Altium Content Vault") (part "RES-2"))
    )
    (comp (ref "R234")
      (value "ERJ3EKF1002V")
      (footprint "RESC1609X55X30LL15T15")
      (description "Chip Resistor, 10 KOhm, +/- 1%, 0.1 W, -55 to 155 degC, 0603 (1608 Metric), RoHS, Tape and Reel")
      (fields (field (name "TOLERANCE") "1%") (field (name "MANUFACTURER") "Panasonic"))
      (libsource (lib "Altium Content Vault") (part "RES-2"))
    )
    (comp (ref "R235")
      (value "ERJ3EKF1002V")
      (footprint "RESC1609X55X30LL15T15")
      (description "Chip Resistor, 10 KOhm, +/- 1%, 0.1 W, -55 to 155 degC, 0603 (1608 Metric), RoHS, Tape and Reel")
      (fields (field (name "TOLERANCE") "1%") (field (name "MANUFACTURER") "Panasonic"))
      (libsource (lib "Altium Content Vault") (part "RES-2"))
    )
    (comp (ref "R264")
      (value "ERJ-3EKF1001V")
      (footprint "RESC1608X55X30LL15T15")
      (fields (field (name "MANUFACTURER") "Panasonic"))
      (libsource (lib "Altium Content Vault") (part "RES"))
    )
    (comp (ref "R265")
      (value "ERJ3EKF1002V")
      (footprint "RESC1609X55X30LL15T15")
      (description "Chip Resistor, 10 KOhm, +/- 1%, 0.1 W, -55 to 155 degC, 0603 (1608 Metric), RoHS, Tape and Reel")
      (fields (field (name "TOLERANCE") "1%") (field (name "MANUFACTURER") "Panasonic"))
      (libsource (lib "Altium Content Vault") (part "RES-2"))
    )
    (comp (ref "R266")
      (value "ERJ3EKF1002V")
      (footprint "RESC1609X55X30LL15T15")
      (description "Chip Resistor, 10 KOhm, +/- 1%, 0.1 W, -55 to 155 degC, 0603 (1608 Metric), RoHS, Tape and Reel")
      (fields (field (name "TOLERANCE") "1%") (field (name "MANUFACTURER") "Panasonic"))
      (libsource (lib "Altium Content Vault") (part "RES-2"))
    )
    (comp (ref "R267")
      (value "ERJ-3EKF1001V")
      (footprint "RESC1608X55X30LL15T15")
      (fields (field (name "MANUFACTURER") "Panasonic"))
      (libsource (lib "Altium Content Vault") (part "RES"))
    )
    (comp (ref "R268")
      (value "ERJ3EKF1002V")
      (footprint "RESC1609X55X30LL15T15")
      (description "Chip Resistor, 10 KOhm, +/- 1%, 0.1 W, -55 to 155 degC, 0603 (1608 Metric), RoHS, Tape and Reel")
      (fields (field (name "TOLERANCE") "1%") (field (name "MANUFACTURER") "Panasonic"))
      (libsource (lib "Altium Content Vault") (part "RES-2"))
    )
    (comp (ref "R269")
      (value "ERJ3EKF1002V")
      (footprint "RESC1609X55X30LL15T15")
      (description "Chip Resistor, 10 KOhm, +/- 1%, 0.1 W, -55 to 155 degC, 0603 (1608 Metric), RoHS, Tape and Reel")
      (fields (field (name "TOLERANCE") "1%") (field (name "MANUFACTURER") "Panasonic"))
      (libsource (lib "Altium Content Vault") (part "RES-2"))
    )
    (comp (ref "R270")
      (value "ERJ-3EKF1001V")
      (footprint "RESC1608X55X30LL15T15")
      (fields (field (name "MANUFACTURER") "Panasonic"))
      (libsource (lib "Altium Content Vault") (part "RES"))
    )
    (comp (ref "R271")
      (value "ERJ3EKF1002V")
      (footprint "RESC1609X55X30LL15T15")
      (description "Chip Resistor, 10 KOhm, +/- 1%, 0.1 W, -55 to 155 degC, 0603 (1608 Metric), RoHS, Tape and Reel")
      (fields (field (name "TOLERANCE") "1%") (field (name "MANUFACTURER") "Panasonic"))
      (libsource (lib "Altium Content Vault") (part "RES-2"))
    )
    (comp (ref "R272")
      (value "ERJ3EKF1002V")
      (footprint "RESC1609X55X30LL15T15")
      (description "Chip Resistor, 10 KOhm, +/- 1%, 0.1 W, -55 to 155 degC, 0603 (1608 Metric), RoHS, Tape and Reel")
      (fields (field (name "TOLERANCE") "1%") (field (name "MANUFACTURER") "Panasonic"))
      (libsource (lib "Altium Content Vault") (part "RES-2"))
    )
    (comp (ref "R273")
      (value "ERJ-3EKF1001V")
      (footprint "RESC1608X55X30LL15T15")
      (fields (field (name "MANUFACTURER") "Panasonic"))
      (libsource (lib "Altium Content Vault") (part "RES"))
    )
    (comp (ref "R274")
      (value "ERJ3EKF1002V")
      (footprint "RESC1609X55X30LL15T15")
      (description "Chip Resistor, 10 KOhm, +/- 1%, 0.1 W, -55 to 155 degC, 0603 (1608 Metric), RoHS, Tape and Reel")
      (fields (field (name "TOLERANCE") "1%") (field (name "MANUFACTURER") "Panasonic"))
      (libsource (lib "Altium Content Vault") (part "RES-2"))
    )
    (comp (ref "R275")
      (value "ERJ3EKF1002V")
      (footprint "RESC1609X55X30LL15T15")
      (description "Chip Resistor, 10 KOhm, +/- 1%, 0.1 W, -55 to 155 degC, 0603 (1608 Metric), RoHS, Tape and Reel")
      (fields (field (name "TOLERANCE") "1%") (field (name "MANUFACTURER") "Panasonic"))
      (libsource (lib "Altium Content Vault") (part "RES-2"))
    )
    (comp (ref "R276")
      (value "ERJ-3EKF1001V")
      (footprint "RESC1608X55X30LL15T15")
      (fields (field (name "MANUFACTURER") "Panasonic"))
      (libsource (lib "Altium Content Vault") (part "RES"))
    )
    (comp (ref "R316")
      (value "ERJ-3EKF1003V")
      (footprint "RESC1608X55X30ML15T15")
      (fields (field (name "MANUFACTURER") "Panasonic"))
      (libsource (lib "Altium Content Vault") (part "RES"))
    )
    (comp (ref "R355")
      (value "ERJ-3EKF1003V")
      (footprint "RESC1608X55X30ML15T15")
      (fields (field (name "MANUFACTURER") "Panasonic"))
      (libsource (lib "Altium Content Vault") (part "RES"))
    )
    (comp (ref "TP17")
      (value "TPAD6R")
      (footprint "New footprint 1")
      (description "Test Point .6mm")
      (libsource (lib "Space Concordia") (part "TP"))
    )
    (comp (ref "TP18")
      (value "TPAD6R")
      (footprint "New footprint 1")
      (description "Test Point .6mm")
      (libsource (lib "Space Concordia") (part "TP"))
    )
    (comp (ref "TP21")
      (value "TPAD6R")
      (footprint "New footprint 1")
      (description "Test Point .6mm")
      (libsource (lib "Space Concordia") (part "TP"))
    )
    (comp (ref "TP88")
      (value "TPAD6R")
      (footprint "New footprint 1")
      (description "Test Point .6mm")
      (libsource (lib "Space Concordia") (part "TP"))
    )
    (comp (ref "TP89")
      (value "TPAD6R")
      (footprint "New footprint 1")
      (description "Test Point .6mm")
      (libsource (lib "Space Concordia") (part "TP"))
    )
    (comp (ref "U11")
      (value "SN74LVC1G07DCKR")
      (footprint "FP-DCK0005A-IPC_C")
      (description "IC BUFF/DVR NON-INVERT SC70-5")
      (libsource (lib "Altium Content Vault") (part "8ab337023d36144ede9cc3383aed264"))
    )
    (comp (ref "U12")
      (value "SN74LVC1G07DCKR")
      (footprint "FP-DCK0005A-IPC_C")
      (description "IC BUFF/DVR NON-INVERT SC70-5")
      (libsource (lib "Altium Content Vault") (part "8ab337023d36144ede9cc3383aed264"))
    )
    (comp (ref "U24")
      (value "LD1117S18TR")
      (footprint "SOT-223_M")
      (description "Fixed Low Drop Positive Voltage Regulator, 1.8V, 4-Pin SOT-223, Tape and Reel")
      (libsource (lib "Altium Content Vault") (part "PM-REG-LD1117-SOT4"))
    )
  )
  (nets
    (net (code "1") (name "/1V8_CAM0_PWDN") (class "Default")
      (node (ref "J1") (pin "114") (pinfunction "114_114") (pintype "passive"))
      (node (ref "R128") (pin "1") (pinfunction "1_1") (pintype "passive"))
    )
    (net (code "2") (name "/1V8_CAM1_PWDN") (class "Default")
      (node (ref "J1") (pin "120") (pinfunction "120_120") (pintype "passive"))
      (node (ref "R129") (pin "1") (pinfunction "1_1") (pintype "passive"))
    )
    (net (code "3") (name "/1V8_SMB_nALERT") (class "Default")
      (node (ref "R176") (pin "1") (pinfunction "1_1") (pintype "passive"))
      (node (ref "U12") (pin "2") (pinfunction "A_2") (pintype "input"))
    )
    (net (code "4") (name "/1V8_SPI1_MISO") (class "Default")
      (node (ref "D3") (pin "4") (pinfunction "IO3_4") (pintype "bidirectional"))
      (node (ref "D3") (pin "7") (pinfunction "NC_7") (pintype "passive"))
      (node (ref "J1") (pin "108") (pinfunction "108_108") (pintype "passive"))
      (node (ref "Q20") (pin "2") (pinfunction "S_2") (pintype "passive"))
      (node (ref "R268") (pin "1") (pinfunction "1_1") (pintype "passive"))
    )
    (net (code "5") (name "/1V8_SPI1_MOSI") (class "Default")
      (node (ref "D3") (pin "1") (pinfunction "IO1_1") (pintype "bidirectional"))
      (node (ref "D3") (pin "10") (pinfunction "NC_10") (pintype "passive"))
      (node (ref "J1") (pin "104") (pinfunction "104_104") (pintype "passive"))
      (node (ref "Q18") (pin "2") (pinfunction "S_2") (pintype "passive"))
      (node (ref "R234") (pin "1") (pinfunction "1_1") (pintype "passive"))
    )
    (net (code "6") (name "/1V8_SPI1_SCLK") (class "Default")
      (node (ref "D3") (pin "2") (pinfunction "IO2_2") (pintype "bidirectional"))
      (node (ref "D3") (pin "9") (pinfunction "NC_9") (pintype "passive"))
      (node (ref "J1") (pin "106") (pinfunction "106_106") (pintype "passive"))
      (node (ref "Q19") (pin "2") (pinfunction "S_2") (pintype "passive"))
      (node (ref "R265") (pin "1") (pinfunction "1_1") (pintype "passive"))
    )
    (net (code "7") (name "/1V8_SPI1_nCS_0") (class "Default")
      (node (ref "D3") (pin "5") (pinfunction "IO4_5") (pintype "bidirectional"))
      (node (ref "D3") (pin "6") (pinfunction "NC_6") (pintype "passive"))
      (node (ref "J1") (pin "110") (pinfunction "110_110") (pintype "passive"))
      (node (ref "Q21") (pin "2") (pinfunction "S_2") (pintype "passive"))
      (node (ref "R271") (pin "1") (pinfunction "1_1") (pintype "passive"))
    )
    (net (code "8") (name "/1V8_SPI1_nCS_1") (class "Default")
      (node (ref "J1") (pin "112") (pinfunction "112_112") (pintype "passive"))
      (node (ref "Q22") (pin "2") (pinfunction "S_2") (pintype "passive"))
      (node (ref "R274") (pin "1") (pinfunction "1_1") (pintype "passive"))
    )
    (net (code "9") (name "/CAM0_PWDN") (class "Default")
      (node (ref "Q9") (pin "6") (pinfunction "Drain1_6") (pintype "passive"))
    )
    (net (code "10") (name "/CAM1_PWDN") (class "Default")
      (node (ref "Q9") (pin "3") (pinfunction "Drain2_3") (pintype "passive"))
    )
    (net (code "11") (name "/CAM_I2C_SCL") (class "Default")
      (node (ref "D18") (pin "4") (pinfunction "IO3_4") (pintype "bidirectional"))
      (node (ref "D18") (pin "7") (pinfunction "NC_7") (pintype "passive"))
      (node (ref "J1") (pin "213") (pinfunction "213_213") (pintype "passive"))
    )
    (net (code "12") (name "/CAM_I2C_SDA") (class "Default")
      (node (ref "D18") (pin "5") (pinfunction "IO4_5") (pintype "bidirectional"))
      (node (ref "D18") (pin "6") (pinfunction "NC_6") (pintype "passive"))
      (node (ref "J1") (pin "215") (pinfunction "215_215") (pintype "passive"))
    )
    (net (code "13") (name "/CAN_RX") (class "Default")
      (node (ref "D17") (pin "1") (pinfunction "IO1_1") (pintype "bidirectional"))
      (node (ref "D17") (pin "10") (pinfunction "NC_10") (pintype "passive"))
      (node (ref "J1") (pin "143") (pinfunction "143_143") (pintype "passive"))
    )
    (net (code "14") (name "/CAN_TX") (class "Default")
      (node (ref "D17") (pin "2") (pinfunction "IO2_2") (pintype "bidirectional"))
      (node (ref "D17") (pin "9") (pinfunction "NC_9") (pintype "passive"))
      (node (ref "J1") (pin "145") (pinfunction "145_145") (pintype "passive"))
    )
    (net (code "15") (name "/CSI0_CLK_N") (class "Default")
      (node (ref "D6") (pin "2") (pinfunction "IO2_2") (pintype "bidirectional"))
      (node (ref "D6") (pin "9") (pinfunction "NC_9") (pintype "passive"))
      (node (ref "J1") (pin "10") (pinfunction "10_10") (pintype "passive"))
    )
    (net (code "16") (name "/CSI0_CLK_P") (class "Default")
      (node (ref "D6") (pin "1") (pinfunction "IO1_1") (pintype "bidirectional"))
      (node (ref "D6") (pin "10") (pinfunction "NC_10") (pintype "passive"))
      (node (ref "J1") (pin "12") (pinfunction "12_12") (pintype "passive"))
    )
    (net (code "17") (name "/CSI0_D0_N") (class "Default")
      (node (ref "D6") (pin "5") (pinfunction "IO4_5") (pintype "bidirectional"))
      (node (ref "D6") (pin "6") (pinfunction "NC_6") (pintype "passive"))
      (node (ref "J1") (pin "4") (pinfunction "4_4") (pintype "passive"))
    )
    (net (code "18") (name "/CSI0_D0_P") (class "Default")
      (node (ref "D6") (pin "4") (pinfunction "IO3_4") (pintype "bidirectional"))
      (node (ref "D6") (pin "7") (pinfunction "NC_7") (pintype "passive"))
      (node (ref "J1") (pin "6") (pinfunction "6_6") (pintype "passive"))
    )
    (net (code "19") (name "/CSI0_D1_N") (class "Default")
      (node (ref "R3") (pin "2") (pinfunction "2_2") (pintype "passive"))
    )
    (net (code "20") (name "/CSI0_D1_P") (class "Default")
      (node (ref "R4") (pin "2") (pinfunction "2_2") (pintype "passive"))
    )
    (net (code "21") (name "/CSI1_D0_N") (class "Default")
      (node (ref "R5") (pin "2") (pinfunction "2_2") (pintype "passive"))
    )
    (net (code "22") (name "/CSI1_D0_P") (class "Default")
      (node (ref "R6") (pin "2") (pinfunction "2_2") (pintype "passive"))
    )
    (net (code "23") (name "/CSI1_D1_N") (class "Default")
      (node (ref "D7") (pin "4") (pinfunction "IO3_4") (pintype "bidirectional"))
      (node (ref "D7") (pin "7") (pinfunction "NC_7") (pintype "passive"))
      (node (ref "J1") (pin "15") (pinfunction "15_15") (pintype "passive"))
    )
    (net (code "24") (name "/CSI1_D1_P") (class "Default")
      (node (ref "D7") (pin "5") (pinfunction "IO4_5") (pintype "bidirectional"))
      (node (ref "D7") (pin "6") (pinfunction "NC_6") (pintype "passive"))
      (node (ref "J1") (pin "17") (pinfunction "17_17") (pintype "passive"))
    )
    (net (code "25") (name "/CSI2_CLK_N") (class "Default")
      (node (ref "D19") (pin "1") (pinfunction "IO1_1") (pintype "bidirectional"))
      (node (ref "D19") (pin "10") (pinfunction "NC_10") (pintype "passive"))
      (node (ref "J1") (pin "28") (pinfunction "28_28") (pintype "passive"))
    )
    (net (code "26") (name "/CSI2_CLK_P") (class "Default")
      (node (ref "D19") (pin "2") (pinfunction "IO2_2") (pintype "bidirectional"))
      (node (ref "D19") (pin "9") (pinfunction "NC_9") (pintype "passive"))
      (node (ref "J1") (pin "30") (pinfunction "30_30") (pintype "passive"))
    )
    (net (code "27") (name "/CSI2_D0_N") (class "Default")
      (node (ref "D13") (pin "4") (pinfunction "IO3_4") (pintype "bidirectional"))
      (node (ref "D13") (pin "7") (pinfunction "NC_7") (pintype "passive"))
      (node (ref "J1") (pin "22") (pinfunction "22_22") (pintype "passive"))
    )
    (net (code "28") (name "/CSI2_D0_P") (class "Default")
      (node (ref "D13") (pin "5") (pinfunction "IO4_5") (pintype "bidirectional"))
      (node (ref "D13") (pin "6") (pinfunction "NC_6") (pintype "passive"))
      (node (ref "J1") (pin "24") (pinfunction "24_24") (pintype "passive"))
    )
    (net (code "29") (name "/CSI2_D1_N") (class "Default")
      (node (ref "D19") (pin "4") (pinfunction "IO3_4") (pintype "bidirectional"))
      (node (ref "D19") (pin "7") (pinfunction "NC_7") (pintype "passive"))
      (node (ref "J1") (pin "34") (pinfunction "34_34") (pintype "passive"))
    )
    (net (code "30") (name "/CSI2_D1_P") (class "Default")
      (node (ref "D19") (pin "5") (pinfunction "IO4_5") (pintype "bidirectional"))
      (node (ref "D19") (pin "6") (pinfunction "NC_6") (pintype "passive"))
      (node (ref "J1") (pin "36") (pinfunction "36_36") (pintype "passive"))
    )
    (net (code "31") (name "/CSI3_D0_N") (class "Default")
      (node (ref "D14") (pin "1") (pinfunction "IO1_1") (pintype "bidirectional"))
      (node (ref "D14") (pin "10") (pinfunction "NC_10") (pintype "passive"))
      (node (ref "J1") (pin "21") (pinfunction "21_21") (pintype "passive"))
    )
    (net (code "32") (name "/CSI3_D0_P") (class "Default")
      (node (ref "D14") (pin "2") (pinfunction "IO2_2") (pintype "bidirectional"))
      (node (ref "D14") (pin "9") (pinfunction "NC_9") (pintype "passive"))
      (node (ref "J1") (pin "23") (pinfunction "23_23") (pintype "passive"))
    )
    (net (code "33") (name "/CSI3_D1_N") (class "Default")
      (node (ref "D14") (pin "4") (pinfunction "IO3_4") (pintype "bidirectional"))
      (node (ref "D14") (pin "7") (pinfunction "NC_7") (pintype "passive"))
      (node (ref "J1") (pin "33") (pinfunction "33_33") (pintype "passive"))
    )
    (net (code "34") (name "/CSI3_D1_P") (class "Default")
      (node (ref "D14") (pin "5") (pinfunction "IO4_5") (pintype "bidirectional"))
      (node (ref "D14") (pin "6") (pinfunction "NC_6") (pintype "passive"))
      (node (ref "J1") (pin "35") (pinfunction "35_35") (pintype "passive"))
    )
    (net (code "35") (name "/DEBUG_RXD") (class "Default")
      (node (ref "R64") (pin "2") (pinfunction "2_2") (pintype "passive"))
    )
    (net (code "36") (name "/DEBUG_TXD") (class "Default")
      (node (ref "R122") (pin "2") (pinfunction "2_2") (pintype "passive"))
    )
    (net (code "37") (name "/DP1_AUX_N") (class "Default")
      (node (ref "D20") (pin "4") (pinfunction "IO3_4") (pintype "bidirectional"))
      (node (ref "D20") (pin "7") (pinfunction "NC_7") (pintype "passive"))
      (node (ref "J1") (pin "98") (pinfunction "98_98") (pintype "passive"))
    )
    (net (code "38") (name "/DP1_AUX_P") (class "Default")
      (node (ref "D20") (pin "5") (pinfunction "IO4_5") (pintype "bidirectional"))
      (node (ref "D20") (pin "6") (pinfunction "NC_6") (pintype "passive"))
      (node (ref "J1") (pin "100") (pinfunction "100_100") (pintype "passive"))
    )
    (net (code "39") (name "/DP1_HPD") (class "Default")
      (node (ref "D20") (pin "2") (pinfunction "IO2_2") (pintype "bidirectional"))
      (node (ref "D20") (pin "9") (pinfunction "NC_9") (pintype "passive"))
      (node (ref "J1") (pin "96") (pinfunction "96_96") (pintype "passive"))
    )
    (net (code "40") (name "/DP1_TXD0_N") (class "Default")
      (node (ref "D8") (pin "1") (pinfunction "IO1_1") (pintype "bidirectional"))
      (node (ref "D8") (pin "10") (pinfunction "NC_10") (pintype "passive"))
      (node (ref "J1") (pin "63") (pinfunction "63_63") (pintype "passive"))
    )
    (net (code "41") (name "/DP1_TXD0_P") (class "Default")
      (node (ref "D8") (pin "2") (pinfunction "IO2_2") (pintype "bidirectional"))
      (node (ref "D8") (pin "9") (pinfunction "NC_9") (pintype "passive"))
      (node (ref "J1") (pin "65") (pinfunction "65_65") (pintype "passive"))
    )
    (net (code "42") (name "/DP1_TXD1_N") (class "Default")
      (node (ref "D8") (pin "4") (pinfunction "IO3_4") (pintype "bidirectional"))
      (node (ref "D8") (pin "7") (pinfunction "NC_7") (pintype "passive"))
      (node (ref "J1") (pin "69") (pinfunction "69_69") (pintype "passive"))
    )
    (net (code "43") (name "/DP1_TXD1_P") (class "Default")
      (node (ref "D8") (pin "5") (pinfunction "IO4_5") (pintype "bidirectional"))
      (node (ref "D8") (pin "6") (pinfunction "NC_6") (pintype "passive"))
      (node (ref "J1") (pin "71") (pinfunction "71_71") (pintype "passive"))
    )
    (net (code "44") (name "/DP1_TXD2_N") (class "Default")
      (node (ref "D15") (pin "1") (pinfunction "IO1_1") (pintype "bidirectional"))
      (node (ref "D15") (pin "10") (pinfunction "NC_10") (pintype "passive"))
      (node (ref "J1") (pin "75") (pinfunction "75_75") (pintype "passive"))
    )
    (net (code "45") (name "/DP1_TXD2_P") (class "Default")
      (node (ref "D15") (pin "2") (pinfunction "IO2_2") (pintype "bidirectional"))
      (node (ref "D15") (pin "9") (pinfunction "NC_9") (pintype "passive"))
      (node (ref "J1") (pin "77") (pinfunction "77_77") (pintype "passive"))
    )
    (net (code "46") (name "/DP1_TXD3_N") (class "Default")
      (node (ref "D15") (pin "4") (pinfunction "IO3_4") (pintype "bidirectional"))
      (node (ref "D15") (pin "7") (pinfunction "NC_7") (pintype "passive"))
      (node (ref "J1") (pin "81") (pinfunction "81_81") (pintype "passive"))
    )
    (net (code "47") (name "/DP1_TXD3_P") (class "Default")
      (node (ref "D15") (pin "5") (pinfunction "IO4_5") (pintype "bidirectional"))
      (node (ref "D15") (pin "6") (pinfunction "NC_6") (pintype "passive"))
      (node (ref "J1") (pin "83") (pinfunction "83_83") (pintype "passive"))
    )
    (net (code "48") (name "/DP_HDMI_CEC") (class "Default")
      (node (ref "D20") (pin "1") (pinfunction "IO1_1") (pintype "bidirectional"))
      (node (ref "D20") (pin "10") (pinfunction "NC_10") (pintype "passive"))
      (node (ref "J1") (pin "94") (pinfunction "94_94") (pintype "passive"))
    )
    (net (code "49") (name "/GBE_LED_ACT") (class "Default")
      (node (ref "J1") (pin "194") (pinfunction "194_194") (pintype "passive"))
    )
    (net (code "50") (name "/GBE_LED_LINK") (class "Default")
      (node (ref "J1") (pin "188") (pinfunction "188_188") (pintype "passive"))
    )
    (net (code "51") (name "/GBE_MDI0_N") (class "Default")
      (node (ref "D5") (pin "1") (pinfunction "IO1_1") (pintype "bidirectional"))
      (node (ref "D5") (pin "10") (pinfunction "NC_10") (pintype "passive"))
      (node (ref "J1") (pin "184") (pinfunction "184_184") (pintype "passive"))
    )
    (net (code "52") (name "/GBE_MDI0_P") (class "Default")
      (node (ref "D5") (pin "2") (pinfunction "IO2_2") (pintype "bidirectional"))
      (node (ref "D5") (pin "9") (pinfunction "NC_9") (pintype "passive"))
      (node (ref "J1") (pin "186") (pinfunction "186_186") (pintype "passive"))
    )
    (net (code "53") (name "/GBE_MDI1_N") (class "Default")
      (node (ref "D5") (pin "4") (pinfunction "IO3_4") (pintype "bidirectional"))
      (node (ref "D5") (pin "7") (pinfunction "NC_7") (pintype "passive"))
      (node (ref "J1") (pin "190") (pinfunction "190_190") (pintype "passive"))
    )
    (net (code "54") (name "/GBE_MDI1_P") (class "Default")
      (node (ref "D5") (pin "5") (pinfunction "IO4_5") (pintype "bidirectional"))
      (node (ref "D5") (pin "6") (pinfunction "NC_6") (pintype "passive"))
      (node (ref "J1") (pin "192") (pinfunction "192_192") (pintype "passive"))
    )
    (net (code "55") (name "/GBE_MDI2_N") (class "Default")
      (node (ref "D12") (pin "1") (pinfunction "IO1_1") (pintype "bidirectional"))
      (node (ref "D12") (pin "10") (pinfunction "NC_10") (pintype "passive"))
      (node (ref "J1") (pin "196") (pinfunction "196_196") (pintype "passive"))
    )
    (net (code "56") (name "/GBE_MDI2_P") (class "Default")
      (node (ref "D12") (pin "2") (pinfunction "IO2_2") (pintype "bidirectional"))
      (node (ref "D12") (pin "9") (pinfunction "NC_9") (pintype "passive"))
      (node (ref "J1") (pin "198") (pinfunction "198_198") (pintype "passive"))
    )
    (net (code "57") (name "/GBE_MDI3_N") (class "Default")
      (node (ref "D12") (pin "4") (pinfunction "IO3_4") (pintype "bidirectional"))
      (node (ref "D12") (pin "7") (pinfunction "NC_7") (pintype "passive"))
      (node (ref "J1") (pin "202") (pinfunction "202_202") (pintype "passive"))
    )
    (net (code "58") (name "/GBE_MDI3_P") (class "Default")
      (node (ref "D12") (pin "5") (pinfunction "IO4_5") (pintype "bidirectional"))
      (node (ref "D12") (pin "6") (pinfunction "NC_6") (pintype "passive"))
      (node (ref "J1") (pin "204") (pinfunction "204_204") (pintype "passive"))
    )
    (net (code "59") (name "/GPIO08_FAN_TACH") (class "Default")
      (node (ref "J1") (pin "208") (pinfunction "208_208") (pintype "passive"))
    )
    (net (code "60") (name "/GPIO10_nSMB_ALERT") (class "Default")
      (node (ref "J1") (pin "212") (pinfunction "212_212") (pintype "passive"))
      (node (ref "R175") (pin "1") (pinfunction "1_1") (pintype "passive"))
      (node (ref "U12") (pin "4") (pinfunction "Y_4") (pintype "output"))
    )
    (net (code "61") (name "/GPIO14_FAN_PWM") (class "Default")
      (node (ref "J1") (pin "230") (pinfunction "230_230") (pintype "passive"))
    )
    (net (code "62") (name "/GPIO_01") (class "Default")
      (node (ref "J1") (pin "118") (pinfunction "118_118") (pintype "passive"))
    )
    (net (code "63") (name "/GPIO_02") (class "Default")
      (node (ref "J1") (pin "124") (pinfunction "124_124") (pintype "passive"))
    )
    (net (code "64") (name "/GPIO_03") (class "Default")
      (node (ref "J1") (pin "126") (pinfunction "126_126") (pintype "passive"))
    )
    (net (code "65") (name "/GPIO_04") (class "Default")
      (node (ref "J1") (pin "127") (pinfunction "127_127") (pintype "passive"))
    )
    (net (code "66") (name "/GPIO_05") (class "Default")
      (node (ref "J1") (pin "128") (pinfunction "128_128") (pintype "passive"))
    )
    (net (code "67") (name "/GPIO_06") (class "Default")
      (node (ref "J1") (pin "130") (pinfunction "130_130") (pintype "passive"))
    )
    (net (code "68") (name "/GPIO_07") (class "Default")
      (node (ref "J1") (pin "206") (pinfunction "206_206") (pintype "passive"))
    )
    (net (code "69") (name "/GPIO_09") (class "Default")
      (node (ref "J1") (pin "211") (pinfunction "211_211") (pintype "passive"))
    )
    (net (code "70") (name "/GPIO_11") (class "Default")
      (node (ref "J1") (pin "216") (pinfunction "216_216") (pintype "passive"))
    )
    (net (code "71") (name "/GPIO_12") (class "Default")
      (node (ref "J1") (pin "218") (pinfunction "218_218") (pintype "passive"))
    )
    (net (code "72") (name "/GPIO_13") (class "Default")
      (node (ref "J1") (pin "228") (pinfunction "228_228") (pintype "passive"))
    )
    (net (code "73") (name "/I2C0_SCL") (class "Default")
      (node (ref "D2") (pin "4") (pinfunction "IO3_4") (pintype "bidirectional"))
      (node (ref "D2") (pin "7") (pinfunction "NC_7") (pintype "passive"))
      (node (ref "J1") (pin "185") (pinfunction "185_185") (pintype "passive"))
    )
    (net (code "74") (name "/I2C0_SDA") (class "Default")
      (node (ref "D2") (pin "5") (pinfunction "IO4_5") (pintype "bidirectional"))
      (node (ref "D2") (pin "6") (pinfunction "NC_6") (pintype "passive"))
      (node (ref "J1") (pin "187") (pinfunction "187_187") (pintype "passive"))
    )
    (net (code "75") (name "/I2C1_SCL") (class "Default")
      (node (ref "J1") (pin "189") (pinfunction "189_189") (pintype "passive"))
    )
    (net (code "76") (name "/I2C1_SDA") (class "Default")
      (node (ref "J1") (pin "191") (pinfunction "191_191") (pintype "passive"))
    )
    (net (code "77") (name "/I2S0_DIN") (class "Default")
      (node (ref "D4") (pin "2") (pinfunction "IO2_2") (pintype "bidirectional"))
      (node (ref "D4") (pin "9") (pinfunction "NC_9") (pintype "passive"))
      (node (ref "J1") (pin "195") (pinfunction "195_195") (pintype "passive"))
      (node (ref "TP17") (pin "1") (pinfunction "TP_1") (pintype "passive"))
    )
    (net (code "78") (name "/I2S0_DOUT") (class "Default")
      (node (ref "D4") (pin "1") (pinfunction "IO1_1") (pintype "bidirectional"))
      (node (ref "D4") (pin "10") (pinfunction "NC_10") (pintype "passive"))
      (node (ref "J1") (pin "193") (pinfunction "193_193") (pintype "passive"))
      (node (ref "TP21") (pin "1") (pinfunction "TP_1") (pintype "passive"))
    )
    (net (code "79") (name "/I2S0_FS") (class "Default")
      (node (ref "D4") (pin "4") (pinfunction "IO3_4") (pintype "bidirectional"))
      (node (ref "D4") (pin "7") (pinfunction "NC_7") (pintype "passive"))
      (node (ref "J1") (pin "197") (pinfunction "197_197") (pintype "passive"))
      (node (ref "TP88") (pin "1") (pinfunction "TP_1") (pintype "passive"))
    )
    (net (code "80") (name "/I2S0_SCLK") (class "Default")
      (node (ref "D4") (pin "5") (pinfunction "IO4_5") (pintype "bidirectional"))
      (node (ref "D4") (pin "6") (pinfunction "NC_6") (pintype "passive"))
      (node (ref "J1") (pin "199") (pinfunction "199_199") (pintype "passive"))
      (node (ref "TP89") (pin "1") (pinfunction "TP_1") (pintype "passive"))
    )
    (net (code "81") (name "/MODULE_ID") (class "Default")
      (node (ref "J1") (pin "217") (pinfunction "217_217") (pintype "passive"))
      (node (ref "R127") (pin "1") (pinfunction "1_1") (pintype "passive"))
    )
    (net (code "82") (name "/PCIE0_CLK_N") (class "Default")
      (node (ref "D1") (pin "1") (pinfunction "IO1_1") (pintype "bidirectional"))
      (node (ref "D1") (pin "10") (pinfunction "NC_10") (pintype "passive"))
      (node (ref "J1") (pin "160") (pinfunction "160_160") (pintype "passive"))
    )
    (net (code "83") (name "/PCIE0_CLK_P") (class "Default")
      (node (ref "D1") (pin "2") (pinfunction "IO2_2") (pintype "bidirectional"))
      (node (ref "D1") (pin "9") (pinfunction "NC_9") (pintype "passive"))
      (node (ref "J1") (pin "162") (pinfunction "162_162") (pintype "passive"))
    )
    (net (code "84") (name "/PCIE0_RX0_N") (class "Default")
      (node (ref "D10") (pin "1") (pinfunction "IO1_1") (pintype "bidirectional"))
      (node (ref "D10") (pin "10") (pinfunction "NC_10") (pintype "passive"))
      (node (ref "J1") (pin "131") (pinfunction "131_131") (pintype "passive"))
    )
    (net (code "85") (name "/PCIE0_RX0_P") (class "Default")
      (node (ref "D10") (pin "2") (pinfunction "IO2_2") (pintype "bidirectional"))
      (node (ref "D10") (pin "9") (pinfunction "NC_9") (pintype "passive"))
      (node (ref "J1") (pin "133") (pinfunction "133_133") (pintype "passive"))
    )
    (net (code "86") (name "/PCIE0_RX1_N") (class "Default")
      (node (ref "D10") (pin "4") (pinfunction "IO3_4") (pintype "bidirectional"))
      (node (ref "D10") (pin "7") (pinfunction "NC_7") (pintype "passive"))
      (node (ref "J1") (pin "137") (pinfunction "137_137") (pintype "passive"))
    )
    (net (code "87") (name "/PCIE0_RX1_P") (class "Default")
      (node (ref "D10") (pin "5") (pinfunction "IO4_5") (pintype "bidirectional"))
      (node (ref "D10") (pin "6") (pinfunction "NC_6") (pintype "passive"))
      (node (ref "J1") (pin "139") (pinfunction "139_139") (pintype "passive"))
    )
    (net (code "88") (name "/PCIE0_RX2_N") (class "Default")
      (node (ref "D17") (pin "4") (pinfunction "IO3_4") (pintype "bidirectional"))
      (node (ref "D17") (pin "7") (pinfunction "NC_7") (pintype "passive"))
      (node (ref "J1") (pin "149") (pinfunction "149_149") (pintype "passive"))
    )
    (net (code "89") (name "/PCIE0_RX2_P") (class "Default")
      (node (ref "D17") (pin "5") (pinfunction "IO4_5") (pintype "bidirectional"))
      (node (ref "D17") (pin "6") (pinfunction "NC_6") (pintype "passive"))
      (node (ref "J1") (pin "151") (pinfunction "151_151") (pintype "passive"))
    )
    (net (code "90") (name "/PCIE0_RX3_N") (class "Default")
      (node (ref "D16") (pin "1") (pinfunction "IO1_1") (pintype "bidirectional"))
      (node (ref "D16") (pin "10") (pinfunction "NC_10") (pintype "passive"))
      (node (ref "J1") (pin "155") (pinfunction "155_155") (pintype "passive"))
    )
    (net (code "91") (name "/PCIE0_RX3_P") (class "Default")
      (node (ref "D16") (pin "2") (pinfunction "IO2_2") (pintype "bidirectional"))
      (node (ref "D16") (pin "9") (pinfunction "NC_9") (pintype "passive"))
      (node (ref "J1") (pin "157") (pinfunction "157_157") (pintype "passive"))
    )
    (net (code "92") (name "/PCIE0_TX0_N") (class "Default")
      (node (ref "D21") (pin "1") (pinfunction "IO1_1") (pintype "bidirectional"))
      (node (ref "D21") (pin "10") (pinfunction "NC_10") (pintype "passive"))
      (node (ref "J1") (pin "134") (pinfunction "134_134") (pintype "passive"))
    )
    (net (code "93") (name "/PCIE0_TX0_P") (class "Default")
      (node (ref "D21") (pin "2") (pinfunction "IO2_2") (pintype "bidirectional"))
      (node (ref "D21") (pin "9") (pinfunction "NC_9") (pintype "passive"))
      (node (ref "J1") (pin "136") (pinfunction "136_136") (pintype "passive"))
    )
    (net (code "94") (name "/PCIE0_TX1_N") (class "Default")
      (node (ref "D21") (pin "4") (pinfunction "IO3_4") (pintype "bidirectional"))
      (node (ref "D21") (pin "7") (pinfunction "NC_7") (pintype "passive"))
      (node (ref "J1") (pin "140") (pinfunction "140_140") (pintype "passive"))
    )
    (net (code "95") (name "/PCIE0_TX1_P") (class "Default")
      (node (ref "D21") (pin "5") (pinfunction "IO4_5") (pintype "bidirectional"))
      (node (ref "D21") (pin "6") (pinfunction "NC_6") (pintype "passive"))
      (node (ref "J1") (pin "142") (pinfunction "142_142") (pintype "passive"))
    )
    (net (code "96") (name "/PCIE0_TX2_N") (class "Default")
      (node (ref "D11") (pin "1") (pinfunction "IO1_1") (pintype "bidirectional"))
      (node (ref "D11") (pin "10") (pinfunction "NC_10") (pintype "passive"))
      (node (ref "J1") (pin "148") (pinfunction "148_148") (pintype "passive"))
    )
    (net (code "97") (name "/PCIE0_TX2_P") (class "Default")
      (node (ref "D11") (pin "2") (pinfunction "IO2_2") (pintype "bidirectional"))
      (node (ref "D11") (pin "9") (pinfunction "NC_9") (pintype "passive"))
      (node (ref "J1") (pin "150") (pinfunction "150_150") (pintype "passive"))
    )
    (net (code "98") (name "/PCIE0_TX3_N") (class "Default")
      (node (ref "D11") (pin "4") (pinfunction "IO3_4") (pintype "bidirectional"))
      (node (ref "D11") (pin "7") (pinfunction "NC_7") (pintype "passive"))
      (node (ref "J1") (pin "154") (pinfunction "154_154") (pintype "passive"))
    )
    (net (code "99") (name "/PCIE0_TX3_P") (class "Default")
      (node (ref "D11") (pin "5") (pinfunction "IO4_5") (pintype "bidirectional"))
      (node (ref "D11") (pin "6") (pinfunction "NC_6") (pintype "passive"))
      (node (ref "J1") (pin "156") (pinfunction "156_156") (pintype "passive"))
    )
    (net (code "100") (name "/PCIE0_nCLKREQ") (class "Default")
      (node (ref "J1") (pin "180") (pinfunction "180_180") (pintype "passive"))
    )
    (net (code "101") (name "/PCIE0_nRST") (class "Default")
      (node (ref "D2") (pin "2") (pinfunction "IO2_2") (pintype "bidirectional"))
      (node (ref "D2") (pin "9") (pinfunction "NC_9") (pintype "passive"))
      (node (ref "J1") (pin "181") (pinfunction "181_181") (pintype "passive"))
    )
    (net (code "102") (name "/PCIE_32K_CLK") (class "Default")
      (node (ref "R174") (pin "1") (pinfunction "1_1") (pintype "passive"))
      (node (ref "U11") (pin "4") (pinfunction "Y_4") (pintype "output"))
    )
    (net (code "103") (name "/PCIE_WAKE") (class "Default")
      (node (ref "D2") (pin "1") (pinfunction "IO1_1") (pintype "bidirectional"))
      (node (ref "D2") (pin "10") (pinfunction "NC_10") (pintype "passive"))
      (node (ref "J1") (pin "179") (pinfunction "179_179") (pintype "passive"))
    )
    (net (code "104") (name "/PMIC_BBAT") (class "Default")
      (node (ref "J1") (pin "235") (pinfunction "235_235") (pintype "passive"))
      (node (ref "TP18") (pin "1") (pinfunction "TP_1") (pintype "passive"))
    )
    (net (code "105") (name "/POWER_EN") (class "Default")
      (node (ref "J1") (pin "237") (pinfunction "237_237") (pintype "passive"))
    )
    (net (code "106") (name "/PRE_CSI0_D1_N") (class "Default")
      (node (ref "D13") (pin "1") (pinfunction "IO1_1") (pintype "bidirectional"))
      (node (ref "D13") (pin "10") (pinfunction "NC_10") (pintype "passive"))
      (node (ref "J1") (pin "16") (pinfunction "16_16") (pintype "passive"))
      (node (ref "R3") (pin "1") (pinfunction "1_1") (pintype "passive"))
    )
    (net (code "107") (name "/PRE_CSI0_D1_P") (class "Default")
      (node (ref "D13") (pin "2") (pinfunction "IO2_2") (pintype "bidirectional"))
      (node (ref "D13") (pin "9") (pinfunction "NC_9") (pintype "passive"))
      (node (ref "J1") (pin "18") (pinfunction "18_18") (pintype "passive"))
      (node (ref "R4") (pin "1") (pinfunction "1_1") (pintype "passive"))
    )
    (net (code "108") (name "/PRE_CSI1_D0_N") (class "Default")
      (node (ref "D7") (pin "1") (pinfunction "IO1_1") (pintype "bidirectional"))
      (node (ref "D7") (pin "10") (pinfunction "NC_10") (pintype "passive"))
      (node (ref "J1") (pin "3") (pinfunction "3_3") (pintype "passive"))
      (node (ref "R5") (pin "1") (pinfunction "1_1") (pintype "passive"))
    )
    (net (code "109") (name "/PRE_CSI1_D0_P") (class "Default")
      (node (ref "D7") (pin "2") (pinfunction "IO2_2") (pintype "bidirectional"))
      (node (ref "D7") (pin "9") (pinfunction "NC_9") (pintype "passive"))
      (node (ref "J1") (pin "5") (pinfunction "5_5") (pintype "passive"))
      (node (ref "R6") (pin "1") (pinfunction "1_1") (pintype "passive"))
    )
    (net (code "110") (name "/PRE_PCIE_32K_CLK") (class "Default")
      (node (ref "J1") (pin "210") (pinfunction "210_210") (pintype "passive"))
      (node (ref "U11") (pin "2") (pinfunction "A_2") (pintype "input"))
    )
    (net (code "111") (name "/SLEEP{slash}nWAKE") (class "Default")
      (node (ref "J1") (pin "240") (pinfunction "240_240") (pintype "passive"))
      (node (ref "R316") (pin "2") (pinfunction "2_2") (pintype "passive"))
    )
    (net (code "112") (name "/SPI1_MISO") (class "Default")
      (node (ref "R270") (pin "2") (pinfunction "2_2") (pintype "passive"))
    )
    (net (code "113") (name "/SPI1_MOSI") (class "Default")
      (node (ref "R264") (pin "2") (pinfunction "2_2") (pintype "passive"))
    )
    (net (code "114") (name "/SPI1_SCLK") (class "Default")
      (node (ref "R267") (pin "2") (pinfunction "2_2") (pintype "passive"))
    )
    (net (code "115") (name "/SPI1_nCS_0") (class "Default")
      (node (ref "R273") (pin "2") (pinfunction "2_2") (pintype "passive"))
    )
    (net (code "116") (name "/SPI1_nCS_1") (class "Default")
      (node (ref "R276") (pin "2") (pinfunction "2_2") (pintype "passive"))
    )
    (net (code "117") (name "/UART2_RXD") (class "Default")
      (node (ref "J1") (pin "238") (pinfunction "238_238") (pintype "passive"))
      (node (ref "Q7") (pin "2") (pinfunction "S_2") (pintype "passive"))
      (node (ref "R62") (pin "1") (pinfunction "1_1") (pintype "passive"))
    )
    (net (code "118") (name "/UART2_TXD") (class "Default")
      (node (ref "J1") (pin "236") (pinfunction "236_236") (pintype "passive"))
      (node (ref "Q8") (pin "2") (pinfunction "S_2") (pintype "passive"))
      (node (ref "R92") (pin "1") (pinfunction "1_1") (pintype "passive"))
    )
    (net (code "119") (name "/USB0_D_N") (class "Default")
      (node (ref "D9") (pin "1") (pinfunction "IO1_1") (pintype "bidirectional"))
      (node (ref "D9") (pin "10") (pinfunction "NC_10") (pintype "passive"))
      (node (ref "J1") (pin "109") (pinfunction "109_109") (pintype "passive"))
    )
    (net (code "120") (name "/USB0_D_P") (class "Default")
      (node (ref "D9") (pin "2") (pinfunction "IO2_2") (pintype "bidirectional"))
      (node (ref "D9") (pin "9") (pinfunction "NC_9") (pintype "passive"))
      (node (ref "J1") (pin "111") (pinfunction "111_111") (pintype "passive"))
    )
    (net (code "121") (name "/USB1_D_N") (class "Default")
      (node (ref "D9") (pin "4") (pinfunction "IO3_4") (pintype "bidirectional"))
      (node (ref "D9") (pin "7") (pinfunction "NC_7") (pintype "passive"))
      (node (ref "J1") (pin "115") (pinfunction "115_115") (pintype "passive"))
    )
    (net (code "122") (name "/USB1_D_P") (class "Default")
      (node (ref "D9") (pin "5") (pinfunction "IO4_5") (pintype "bidirectional"))
      (node (ref "D9") (pin "6") (pinfunction "NC_6") (pintype "passive"))
      (node (ref "J1") (pin "117") (pinfunction "117_117") (pintype "passive"))
    )
    (net (code "123") (name "/USBSS0_RX_N") (class "Default")
      (node (ref "D16") (pin "4") (pinfunction "IO3_4") (pintype "bidirectional"))
      (node (ref "D16") (pin "7") (pinfunction "NC_7") (pintype "passive"))
      (node (ref "J1") (pin "161") (pinfunction "161_161") (pintype "passive"))
    )
    (net (code "124") (name "/USBSS0_RX_P") (class "Default")
      (node (ref "D16") (pin "5") (pinfunction "IO4_5") (pintype "bidirectional"))
      (node (ref "D16") (pin "6") (pinfunction "NC_6") (pintype "passive"))
      (node (ref "J1") (pin "163") (pinfunction "163_163") (pintype "passive"))
    )
    (net (code "125") (name "/USBSS0_TX_N") (class "Default")
      (node (ref "D1") (pin "4") (pinfunction "IO3_4") (pintype "bidirectional"))
      (node (ref "D1") (pin "7") (pinfunction "NC_7") (pintype "passive"))
      (node (ref "J1") (pin "166") (pinfunction "166_166") (pintype "passive"))
    )
    (net (code "126") (name "/USBSS0_TX_P") (class "Default")
      (node (ref "D1") (pin "5") (pinfunction "IO4_5") (pintype "bidirectional"))
      (node (ref "D1") (pin "6") (pinfunction "NC_6") (pintype "passive"))
      (node (ref "J1") (pin "168") (pinfunction "168_168") (pintype "passive"))
    )
    (net (code "127") (name "/VBUS_DETECT") (class "Default")
      (node (ref "J1") (pin "87") (pinfunction "87_87") (pintype "passive"))
    )
    (net (code "128") (name "/nFORCE_RECOVERY") (class "Default")
      (node (ref "J1") (pin "214") (pinfunction "214_214") (pintype "passive"))
      (node (ref "J17") (pin "1") (pinfunction "1_1") (pintype "passive"))
      (node (ref "R355") (pin "1") (pinfunction "1_1") (pintype "passive"))
    )
    (net (code "129") (name "/nMOD_SLEEP") (class "Default")
      (node (ref "J1") (pin "178") (pinfunction "178_178") (pintype "passive"))
    )
    (net (code "130") (name "/nSHUTDOWN_REQ") (class "Default")
      (node (ref "J1") (pin "233") (pinfunction "233_233") (pintype "passive"))
    )
    (net (code "131") (name "/nSYS_RESET") (class "Default")
      (node (ref "J1") (pin "239") (pinfunction "239_239") (pintype "passive"))
    )
    (net (code "132") (name "2V_AUX") (class "Default")
      (node (ref "C214") (pin "2") (pinfunction "2_2") (pintype "passive"))
      (node (ref "U24") (pin "3") (pinfunction "VIN_3") (pintype "power_in"))
    )
    (net (code "133") (name "3V3_AUX") (class "Default")
      (node (ref "R174") (pin "2") (pinfunction "2_2") (pintype "passive"))
      (node (ref "R235") (pin "2") (pinfunction "2_2") (pintype "passive"))
      (node (ref "R266") (pin "2") (pinfunction "2_2") (pintype "passive"))
      (node (ref "R269") (pin "2") (pinfunction "2_2") (pintype "passive"))
      (node (ref "R272") (pin "2") (pinfunction "2_2") (pintype "passive"))
      (node (ref "R275") (pin "2") (pinfunction "2_2") (pintype "passive"))
    )
    (net (code "134") (name "5V_MAIN") (class "Default")
      (node (ref "J1") (pin "251") (pinfunction "251_251") (pintype "passive"))
      (node (ref "J1") (pin "252") (pinfunction "252_252") (pintype "passive"))
      (node (ref "J1") (pin "253") (pinfunction "253_253") (pintype "passive"))
      (node (ref "J1") (pin "254") (pinfunction "254_254") (pintype "passive"))
      (node (ref "J1") (pin "255") (pinfunction "255_255") (pintype "passive"))
      (node (ref "J1") (pin "256") (pinfunction "256_256") (pintype "passive"))
      (node (ref "J1") (pin "257") (pinfunction "257_257") (pintype "passive"))
      (node (ref "J1") (pin "258") (pinfunction "258_258") (pintype "passive"))
      (node (ref "J1") (pin "259") (pinfunction "259_259") (pintype "passive"))
      (node (ref "J1") (pin "260") (pinfunction "260_260") (pintype "passive"))
      (node (ref "R118") (pin "2") (pinfunction "2_2") (pintype "passive"))
      (node (ref "R63") (pin "2") (pinfunction "2_2") (pintype "passive"))
    )
    (net (code "135") (name "GND") (class "Default")
      (node (ref "C103") (pin "2") (pinfunction "2_2") (pintype "passive"))
      (node (ref "C116") (pin "2") (pinfunction "2_2") (pintype "passive"))
      (node (ref "C213") (pin "2") (pinfunction "2_2") (pintype "passive"))
      (node (ref "C214") (pin "1") (pinfunction "1_1") (pintype "passive"))
      (node (ref "D1") (pin "3") (pinfunction "GND_3") (pintype "power_in"))
      (node (ref "D1") (pin "8") (pinfunction "GND_8") (pintype "power_in"))
      (node (ref "D10") (pin "3") (pinfunction "GND_3") (pintype "power_in"))
      (node (ref "D10") (pin "8") (pinfunction "GND_8") (pintype "power_in"))
      (node (ref "D11") (pin "3") (pinfunction "GND_3") (pintype "power_in"))
      (node (ref "D11") (pin "8") (pinfunction "GND_8") (pintype "power_in"))
      (node (ref "D12") (pin "3") (pinfunction "GND_3") (pintype "power_in"))
      (node (ref "D12") (pin "8") (pinfunction "GND_8") (pintype "power_in"))
      (node (ref "D13") (pin "3") (pinfunction "GND_3") (pintype "power_in"))
      (node (ref "D13") (pin "8") (pinfunction "GND_8") (pintype "power_in"))
      (node (ref "D14") (pin "3") (pinfunction "GND_3") (pintype "power_in"))
      (node (ref "D14") (pin "8") (pinfunction "GND_8") (pintype "power_in"))
      (node (ref "D15") (pin "3") (pinfunction "GND_3") (pintype "power_in"))
      (node (ref "D15") (pin "8") (pinfunction "GND_8") (pintype "power_in"))
      (node (ref "D16") (pin "3") (pinfunction "GND_3") (pintype "power_in"))
      (node (ref "D16") (pin "8") (pinfunction "GND_8") (pintype "power_in"))
      (node (ref "D17") (pin "3") (pinfunction "GND_3") (pintype "power_in"))
      (node (ref "D17") (pin "8") (pinfunction "GND_8") (pintype "power_in"))
      (node (ref "D18") (pin "3") (pinfunction "GND_3") (pintype "power_in"))
      (node (ref "D18") (pin "8") (pinfunction "GND_8") (pintype "power_in"))
      (node (ref "D19") (pin "3") (pinfunction "GND_3") (pintype "power_in"))
      (node (ref "D19") (pin "8") (pinfunction "GND_8") (pintype "power_in"))
      (node (ref "D2") (pin "3") (pinfunction "GND_3") (pintype "power_in"))
      (node (ref "D2") (pin "8") (pinfunction "GND_8") (pintype "power_in"))
      (node (ref "D20") (pin "3") (pinfunction "GND_3") (pintype "power_in"))
      (node (ref "D20") (pin "8") (pinfunction "GND_8") (pintype "power_in"))
      (node (ref "D21") (pin "3") (pinfunction "GND_3") (pintype "power_in"))
      (node (ref "D21") (pin "8") (pinfunction "GND_8") (pintype "power_in"))
      (node (ref "D3") (pin "3") (pinfunction "GND_3") (pintype "power_in"))
      (node (ref "D3") (pin "8") (pinfunction "GND_8") (pintype "power_in"))
      (node (ref "D4") (pin "3") (pinfunction "GND_3") (pintype "power_in"))
      (node (ref "D4") (pin "8") (pinfunction "GND_8") (pintype "power_in"))
      (node (ref "D5") (pin "3") (pinfunction "GND_3") (pintype "power_in"))
      (node (ref "D5") (pin "8") (pinfunction "GND_8") (pintype "power_in"))
      (node (ref "D6") (pin "3") (pinfunction "GND_3") (pintype "power_in"))
      (node (ref "D6") (pin "8") (pinfunction "GND_8") (pintype "power_in"))
      (node (ref "D7") (pin "3") (pinfunction "GND_3") (pintype "power_in"))
      (node (ref "D7") (pin "8") (pinfunction "GND_8") (pintype "power_in"))
      (node (ref "D8") (pin "3") (pinfunction "GND_3") (pintype "power_in"))
      (node (ref "D8") (pin "8") (pinfunction "GND_8") (pintype "power_in"))
      (node (ref "D9") (pin "3") (pinfunction "GND_3") (pintype "power_in"))
      (node (ref "D9") (pin "8") (pinfunction "GND_8") (pintype "power_in"))
      (node (ref "J1") (pin "1") (pinfunction "1_1") (pintype "passive"))
      (node (ref "J1") (pin "102") (pinfunction "102_102") (pintype "passive"))
      (node (ref "J1") (pin "107") (pinfunction "107_107") (pintype "passive"))
      (node (ref "J1") (pin "113") (pinfunction "113_113") (pintype "passive"))
      (node (ref "J1") (pin "119") (pinfunction "119_119") (pintype "passive"))
      (node (ref "J1") (pin "125") (pinfunction "125_125") (pintype "passive"))
      (node (ref "J1") (pin "129") (pinfunction "129_129") (pintype "passive"))
      (node (ref "J1") (pin "13") (pinfunction "13_13") (pintype "passive"))
      (node (ref "J1") (pin "132") (pinfunction "132_132") (pintype "passive"))
      (node (ref "J1") (pin "135") (pinfunction "135_135") (pintype "passive"))
      (node (ref "J1") (pin "138") (pinfunction "138_138") (pintype "passive"))
      (node (ref "J1") (pin "14") (pinfunction "14_14") (pintype "passive"))
      (node (ref "J1") (pin "141") (pinfunction "141_141") (pintype "passive"))
      (node (ref "J1") (pin "144") (pinfunction "144_144") (pintype "passive"))
      (node (ref "J1") (pin "146") (pinfunction "146_146") (pintype "passive"))
      (node (ref "J1") (pin "147") (pinfunction "147_147") (pintype "passive"))
      (node (ref "J1") (pin "152") (pinfunction "152_152") (pintype "passive"))
      (node (ref "J1") (pin "153") (pinfunction "153_153") (pintype "passive"))
      (node (ref "J1") (pin "158") (pinfunction "158_158") (pintype "passive"))
      (node (ref "J1") (pin "159") (pinfunction "159_159") (pintype "passive"))
      (node (ref "J1") (pin "164") (pinfunction "164_164") (pintype "passive"))
      (node (ref "J1") (pin "165") (pinfunction "165_165") (pintype "passive"))
      (node (ref "J1") (pin "170") (pinfunction "170_170") (pintype "passive"))
      (node (ref "J1") (pin "171") (pinfunction "171_171") (pintype "passive"))
      (node (ref "J1") (pin "176") (pinfunction "176_176") (pintype "passive"))
      (node (ref "J1") (pin "177") (pinfunction "177_177") (pintype "passive"))
      (node (ref "J1") (pin "19") (pinfunction "19_19") (pintype "passive"))
      (node (ref "J1") (pin "2") (pinfunction "2_2") (pintype "passive"))
      (node (ref "J1") (pin "20") (pinfunction "20_20") (pintype "passive"))
      (node (ref "J1") (pin "200") (pinfunction "200_200") (pintype "passive"))
      (node (ref "J1") (pin "201") (pinfunction "201_201") (pintype "passive"))
      (node (ref "J1") (pin "231") (pinfunction "231_231") (pintype "passive"))
      (node (ref "J1") (pin "241") (pinfunction "241_241") (pintype "passive"))
      (node (ref "J1") (pin "242") (pinfunction "242_242") (pintype "passive"))
      (node (ref "J1") (pin "243") (pinfunction "243_243") (pintype "passive"))
      (node (ref "J1") (pin "244") (pinfunction "244_244") (pintype "passive"))
      (node (ref "J1") (pin "245") (pinfunction "245_245") (pintype "passive"))
      (node (ref "J1") (pin "246") (pinfunction "246_246") (pintype "passive"))
      (node (ref "J1") (pin "247") (pinfunction "247_247") (pintype "passive"))
      (node (ref "J1") (pin "248") (pinfunction "248_248") (pintype "passive"))
      (node (ref "J1") (pin "249") (pinfunction "249_249") (pintype "passive"))
      (node (ref "J1") (pin "25") (pinfunction "25_25") (pintype "passive"))
      (node (ref "J1") (pin "250") (pinfunction "250_250") (pintype "passive"))
      (node (ref "J1") (pin "26") (pinfunction "26_26") (pintype "passive"))
      (node (ref "J1") (pin "261") (pinfunction "MNT_1_261") (pintype "passive"))
      (node (ref "J1") (pin "262") (pinfunction "MNT_2_262") (pintype "passive"))
      (node (ref "J1") (pin "31") (pinfunction "31_31") (pintype "passive"))
      (node (ref "J1") (pin "32") (pinfunction "32_32") (pintype "passive"))
      (node (ref "J1") (pin "37") (pinfunction "37_37") (pintype "passive"))
      (node (ref "J1") (pin "38") (pinfunction "38_38") (pintype "passive"))
      (node (ref "J1") (pin "43") (pinfunction "43_43") (pintype "passive"))
      (node (ref "J1") (pin "44") (pinfunction "44_44") (pintype "passive"))
      (node (ref "J1") (pin "49") (pinfunction "49_49") (pintype "passive"))
      (node (ref "J1") (pin "50") (pinfunction "50_50") (pintype "passive"))
      (node (ref "J1") (pin "55") (pinfunction "55_55") (pintype "passive"))
      (node (ref "J1") (pin "56") (pinfunction "56_56") (pintype "passive"))
      (node (ref "J1") (pin "61") (pinfunction "61_61") (pintype "passive"))
      (node (ref "J1") (pin "62") (pinfunction "62_62") (pintype "passive"))
      (node (ref "J1") (pin "67") (pinfunction "67_67") (pintype "passive"))
      (node (ref "J1") (pin "68") (pinfunction "68_68") (pintype "passive"))
      (node (ref "J1") (pin "7") (pinfunction "7_7") (pintype "passive"))
      (node (ref "J1") (pin "73") (pinfunction "73_73") (pintype "passive"))
      (node (ref "J1") (pin "74") (pinfunction "74_74") (pintype "passive"))
      (node (ref "J1") (pin "79") (pinfunction "79_79") (pintype "passive"))
      (node (ref "J1") (pin "8") (pinfunction "8_8") (pintype "passive"))
      (node (ref "J1") (pin "80") (pinfunction "80_80") (pintype "passive"))
      (node (ref "J1") (pin "85") (pinfunction "85_85") (pintype "passive"))
      (node (ref "J1") (pin "86") (pinfunction "86_86") (pintype "passive"))
      (node (ref "J17") (pin "2") (pinfunction "2_2") (pintype "passive"))
      (node (ref "MP1") (pin "1") (pinfunction "1_1") (pintype "passive"))
      (node (ref "MP2") (pin "1") (pinfunction "1_1") (pintype "passive"))
      (node (ref "Q9") (pin "1") (pinfunction "Source1_1") (pintype "passive"))
      (node (ref "Q9") (pin "4") (pinfunction "Source2_4") (pintype "passive"))
      (node (ref "R127") (pin "2") (pinfunction "2_2") (pintype "passive"))
      (node (ref "R172") (pin "1") (pinfunction "1_1") (pintype "passive"))
      (node (ref "R173") (pin "1") (pinfunction "1_1") (pintype "passive"))
      (node (ref "R316") (pin "1") (pinfunction "1_1") (pintype "passive"))
      (node (ref "U11") (pin "3") (pinfunction "GND_3") (pintype "power_in"))
      (node (ref "U12") (pin "3") (pinfunction "GND_3") (pintype "power_in"))
      (node (ref "U24") (pin "1") (pinfunction "GND_1") (pintype "power_in"))
    )
    (net (code "136") (name "JETSON_1V8_REF") (class "Default")
      (node (ref "C103") (pin "1") (pinfunction "1_1") (pintype "passive"))
      (node (ref "C116") (pin "1") (pinfunction "1_1") (pintype "passive"))
      (node (ref "C213") (pin "1") (pinfunction "1_1") (pintype "passive"))
      (node (ref "Q18") (pin "1") (pinfunction "G_1") (pintype "passive"))
      (node (ref "Q19") (pin "1") (pinfunction "G_1") (pintype "passive"))
      (node (ref "Q20") (pin "1") (pinfunction "G_1") (pintype "passive"))
      (node (ref "Q21") (pin "1") (pinfunction "G_1") (pintype "passive"))
      (node (ref "Q22") (pin "1") (pinfunction "G_1") (pintype "passive"))
      (node (ref "Q7") (pin "1") (pinfunction "G_1") (pintype "passive"))
      (node (ref "Q8") (pin "1") (pinfunction "G_1") (pintype "passive"))
      (node (ref "R175") (pin "2") (pinfunction "2_2") (pintype "passive"))
      (node (ref "R176") (pin "2") (pinfunction "2_2") (pintype "passive"))
      (node (ref "R234") (pin "2") (pinfunction "2_2") (pintype "passive"))
      (node (ref "R265") (pin "2") (pinfunction "2_2") (pintype "passive"))
      (node (ref "R268") (pin "2") (pinfunction "2_2") (pintype "passive"))
      (node (ref "R271") (pin "2") (pinfunction "2_2") (pintype "passive"))
      (node (ref "R274") (pin "2") (pinfunction "2_2") (pintype "passive"))
      (node (ref "R355") (pin "2") (pinfunction "2_2") (pintype "passive"))
      (node (ref "R62") (pin "2") (pinfunction "2_2") (pintype "passive"))
      (node (ref "R92") (pin "2") (pinfunction "2_2") (pintype "passive"))
      (node (ref "U11") (pin "5") (pinfunction "VCC_5") (pintype "power_in"))
      (node (ref "U12") (pin "5") (pinfunction "VCC_5") (pintype "power_in"))
      (node (ref "U24") (pin "2") (pinfunction "VOUT_2") (pintype "power_in"))
      (node (ref "U24") (pin "4") (pinfunction "VOUT_4") (pintype "power_in"))
    )
    (net (code "137") (name "Net-(Q7-D)") (class "Default")
      (node (ref "Q7") (pin "3") (pinfunction "D_3") (pintype "passive"))
      (node (ref "R63") (pin "1") (pinfunction "1_1") (pintype "passive"))
      (node (ref "R64") (pin "1") (pinfunction "1_1") (pintype "passive"))
    )
    (net (code "138") (name "Net-(Q8-D)") (class "Default")
      (node (ref "Q8") (pin "3") (pinfunction "D_3") (pintype "passive"))
      (node (ref "R118") (pin "1") (pinfunction "1_1") (pintype "passive"))
      (node (ref "R122") (pin "1") (pinfunction "1_1") (pintype "passive"))
    )
    (net (code "139") (name "Net-(Q9A-Gate1)") (class "Default")
      (node (ref "Q9") (pin "2") (pinfunction "Gate1_2") (pintype "passive"))
      (node (ref "R128") (pin "2") (pinfunction "2_2") (pintype "passive"))
      (node (ref "R172") (pin "2") (pinfunction "2_2") (pintype "passive"))
    )
    (net (code "140") (name "Net-(Q9B-Gate2)") (class "Default")
      (node (ref "Q9") (pin "5") (pinfunction "Gate2_5") (pintype "passive"))
      (node (ref "R129") (pin "2") (pinfunction "2_2") (pintype "passive"))
      (node (ref "R173") (pin "2") (pinfunction "2_2") (pintype "passive"))
    )
    (net (code "141") (name "Net-(Q18-D)") (class "Default")
      (node (ref "Q18") (pin "3") (pinfunction "D_3") (pintype "passive"))
      (node (ref "R235") (pin "1") (pinfunction "1_1") (pintype "passive"))
      (node (ref "R264") (pin "1") (pinfunction "1_1") (pintype "passive"))
    )
    (net (code "142") (name "Net-(Q19-D)") (class "Default")
      (node (ref "Q19") (pin "3") (pinfunction "D_3") (pintype "passive"))
      (node (ref "R266") (pin "1") (pinfunction "1_1") (pintype "passive"))
      (node (ref "R267") (pin "1") (pinfunction "1_1") (pintype "passive"))
    )
    (net (code "143") (name "Net-(Q20-D)") (class "Default")
      (node (ref "Q20") (pin "3") (pinfunction "D_3") (pintype "passive"))
      (node (ref "R269") (pin "1") (pinfunction "1_1") (pintype "passive"))
      (node (ref "R270") (pin "1") (pinfunction "1_1") (pintype "passive"))
    )
    (net (code "144") (name "Net-(Q21-D)") (class "Default")
      (node (ref "Q21") (pin "3") (pinfunction "D_3") (pintype "passive"))
      (node (ref "R272") (pin "1") (pinfunction "1_1") (pintype "passive"))
      (node (ref "R273") (pin "1") (pinfunction "1_1") (pintype "passive"))
    )
    (net (code "145") (name "Net-(Q22-D)") (class "Default")
      (node (ref "Q22") (pin "3") (pinfunction "D_3") (pintype "passive"))
      (node (ref "R275") (pin "1") (pinfunction "1_1") (pintype "passive"))
      (node (ref "R276") (pin "1") (pinfunction "1_1") (pintype "passive"))
    )
    (net (code "146") (name "unconnected-(D18-IO1-Pad1)") (class "Default")
      (node (ref "D18") (pin "1") (pinfunction "IO1_1") (pintype "bidirectional"))
    )
    (net (code "147") (name "unconnected-(D18-IO2-Pad2)") (class "Default")
      (node (ref "D18") (pin "2") (pinfunction "IO2_2") (pintype "bidirectional"))
    )
    (net (code "148") (name "unconnected-(D18-NC-Pad9)") (class "Default")
      (node (ref "D18") (pin "9") (pinfunction "NC_9") (pintype "passive"))
    )
    (net (code "149") (name "unconnected-(D18-NC-Pad10)") (class "Default")
      (node (ref "D18") (pin "10") (pinfunction "NC_10") (pintype "passive"))
    )
    (net (code "150") (name "unconnected-(J1-Pad9)") (class "Default")
      (node (ref "J1") (pin "9") (pinfunction "9_9") (pintype "passive+no_connect"))
    )
    (net (code "151") (name "unconnected-(J1-Pad11)") (class "Default")
      (node (ref "J1") (pin "11") (pinfunction "11_11") (pintype "passive+no_connect"))
    )
    (net (code "152") (name "unconnected-(J1-Pad27)") (class "Default")
      (node (ref "J1") (pin "27") (pinfunction "27_27") (pintype "passive+no_connect"))
    )
    (net (code "153") (name "unconnected-(J1-Pad29)") (class "Default")
      (node (ref "J1") (pin "29") (pinfunction "29_29") (pintype "passive+no_connect"))
    )
    (net (code "154") (name "unconnected-(J1-Pad39)") (class "Default")
      (node (ref "J1") (pin "39") (pinfunction "39_39") (pintype "passive+no_connect"))
    )
    (net (code "155") (name "unconnected-(J1-Pad40)") (class "Default")
      (node (ref "J1") (pin "40") (pinfunction "40_40") (pintype "passive+no_connect"))
    )
    (net (code "156") (name "unconnected-(J1-Pad41)") (class "Default")
      (node (ref "J1") (pin "41") (pinfunction "41_41") (pintype "passive+no_connect"))
    )
    (net (code "157") (name "unconnected-(J1-Pad42)") (class "Default")
      (node (ref "J1") (pin "42") (pinfunction "42_42") (pintype "passive+no_connect"))
    )
    (net (code "158") (name "unconnected-(J1-Pad45)") (class "Default")
      (node (ref "J1") (pin "45") (pinfunction "45_45") (pintype "passive+no_connect"))
    )
    (net (code "159") (name "unconnected-(J1-Pad46)") (class "Default")
      (node (ref "J1") (pin "46") (pinfunction "46_46") (pintype "passive+no_connect"))
    )
    (net (code "160") (name "unconnected-(J1-Pad47)") (class "Default")
      (node (ref "J1") (pin "47") (pinfunction "47_47") (pintype "passive+no_connect"))
    )
    (net (code "161") (name "unconnected-(J1-Pad48)") (class "Default")
      (node (ref "J1") (pin "48") (pinfunction "48_48") (pintype "passive+no_connect"))
    )
    (net (code "162") (name "unconnected-(J1-Pad51)") (class "Default")
      (node (ref "J1") (pin "51") (pinfunction "51_51") (pintype "passive+no_connect"))
    )
    (net (code "163") (name "unconnected-(J1-Pad52)") (class "Default")
      (node (ref "J1") (pin "52") (pinfunction "52_52") (pintype "passive+no_connect"))
    )
    (net (code "164") (name "unconnected-(J1-Pad53)") (class "Default")
      (node (ref "J1") (pin "53") (pinfunction "53_53") (pintype "passive+no_connect"))
    )
    (net (code "165") (name "unconnected-(J1-Pad54)") (class "Default")
      (node (ref "J1") (pin "54") (pinfunction "54_54") (pintype "passive+no_connect"))
    )
    (net (code "166") (name "unconnected-(J1-Pad57)") (class "Default")
      (node (ref "J1") (pin "57") (pinfunction "57_57") (pintype "passive+no_connect"))
    )
    (net (code "167") (name "unconnected-(J1-Pad58)") (class "Default")
      (node (ref "J1") (pin "58") (pinfunction "58_58") (pintype "passive+no_connect"))
    )
    (net (code "168") (name "unconnected-(J1-Pad59)") (class "Default")
      (node (ref "J1") (pin "59") (pinfunction "59_59") (pintype "passive+no_connect"))
    )
    (net (code "169") (name "unconnected-(J1-Pad60)") (class "Default")
      (node (ref "J1") (pin "60") (pinfunction "60_60") (pintype "passive+no_connect"))
    )
    (net (code "170") (name "unconnected-(J1-Pad64)") (class "Default")
      (node (ref "J1") (pin "64") (pinfunction "64_64") (pintype "passive+no_connect"))
    )
    (net (code "171") (name "unconnected-(J1-Pad66)") (class "Default")
      (node (ref "J1") (pin "66") (pinfunction "66_66") (pintype "passive+no_connect"))
    )
    (net (code "172") (name "unconnected-(J1-Pad70)") (class "Default")
      (node (ref "J1") (pin "70") (pinfunction "70_70") (pintype "passive+no_connect"))
    )
    (net (code "173") (name "unconnected-(J1-Pad72)") (class "Default")
      (node (ref "J1") (pin "72") (pinfunction "72_72") (pintype "passive+no_connect"))
    )
    (net (code "174") (name "unconnected-(J1-Pad76)") (class "Default")
      (node (ref "J1") (pin "76") (pinfunction "76_76") (pintype "passive+no_connect"))
    )
    (net (code "175") (name "unconnected-(J1-Pad78)") (class "Default")
      (node (ref "J1") (pin "78") (pinfunction "78_78") (pintype "passive+no_connect"))
    )
    (net (code "176") (name "unconnected-(J1-Pad82)") (class "Default")
      (node (ref "J1") (pin "82") (pinfunction "82_82") (pintype "passive+no_connect"))
    )
    (net (code "177") (name "unconnected-(J1-Pad84)") (class "Default")
      (node (ref "J1") (pin "84") (pinfunction "84_84") (pintype "passive+no_connect"))
    )
    (net (code "178") (name "unconnected-(J1-Pad88)") (class "Default")
      (node (ref "J1") (pin "88") (pinfunction "88_88") (pintype "passive+no_connect"))
    )
    (net (code "179") (name "unconnected-(J1-Pad89)") (class "Default")
      (node (ref "J1") (pin "89") (pinfunction "89_89") (pintype "passive+no_connect"))
    )
    (net (code "180") (name "unconnected-(J1-Pad90)") (class "Default")
      (node (ref "J1") (pin "90") (pinfunction "90_90") (pintype "passive+no_connect"))
    )
    (net (code "181") (name "unconnected-(J1-Pad91)") (class "Default")
      (node (ref "J1") (pin "91") (pinfunction "91_91") (pintype "passive+no_connect"))
    )
    (net (code "182") (name "unconnected-(J1-Pad92)") (class "Default")
      (node (ref "J1") (pin "92") (pinfunction "92_92") (pintype "passive+no_connect"))
    )
    (net (code "183") (name "unconnected-(J1-Pad93)") (class "Default")
      (node (ref "J1") (pin "93") (pinfunction "93_93") (pintype "passive+no_connect"))
    )
    (net (code "184") (name "unconnected-(J1-Pad95)") (class "Default")
      (node (ref "J1") (pin "95") (pinfunction "95_95") (pintype "passive+no_connect"))
    )
    (net (code "185") (name "unconnected-(J1-Pad97)") (class "Default")
      (node (ref "J1") (pin "97") (pinfunction "97_97") (pintype "passive+no_connect"))
    )
    (net (code "186") (name "unconnected-(J1-Pad99)") (class "Default")
      (node (ref "J1") (pin "99") (pinfunction "99_99") (pintype "passive+no_connect"))
    )
    (net (code "187") (name "unconnected-(J1-Pad101)") (class "Default")
      (node (ref "J1") (pin "101") (pinfunction "101_101") (pintype "passive+no_connect"))
    )
    (net (code "188") (name "unconnected-(J1-Pad103)") (class "Default")
      (node (ref "J1") (pin "103") (pinfunction "103_103") (pintype "passive+no_connect"))
    )
    (net (code "189") (name "unconnected-(J1-Pad105)") (class "Default")
      (node (ref "J1") (pin "105") (pinfunction "105_105") (pintype "passive+no_connect"))
    )
    (net (code "190") (name "unconnected-(J1-Pad116)") (class "Default")
      (node (ref "J1") (pin "116") (pinfunction "116_116") (pintype "passive+no_connect"))
    )
    (net (code "191") (name "unconnected-(J1-Pad121)") (class "Default")
      (node (ref "J1") (pin "121") (pinfunction "121_121") (pintype "passive+no_connect"))
    )
    (net (code "192") (name "unconnected-(J1-Pad122)") (class "Default")
      (node (ref "J1") (pin "122") (pinfunction "122_122") (pintype "passive+no_connect"))
    )
    (net (code "193") (name "unconnected-(J1-Pad123)") (class "Default")
      (node (ref "J1") (pin "123") (pinfunction "123_123") (pintype "passive+no_connect"))
    )
    (net (code "194") (name "unconnected-(J1-Pad167)") (class "Default")
      (node (ref "J1") (pin "167") (pinfunction "167_167") (pintype "passive+no_connect"))
    )
    (net (code "195") (name "unconnected-(J1-Pad169)") (class "Default")
      (node (ref "J1") (pin "169") (pinfunction "169_169") (pintype "passive+no_connect"))
    )
    (net (code "196") (name "unconnected-(J1-Pad172)") (class "Default")
      (node (ref "J1") (pin "172") (pinfunction "172_172") (pintype "passive+no_connect"))
    )
    (net (code "197") (name "unconnected-(J1-Pad173)") (class "Default")
      (node (ref "J1") (pin "173") (pinfunction "173_173") (pintype "passive+no_connect"))
    )
    (net (code "198") (name "unconnected-(J1-Pad174)") (class "Default")
      (node (ref "J1") (pin "174") (pinfunction "174_174") (pintype "passive+no_connect"))
    )
    (net (code "199") (name "unconnected-(J1-Pad175)") (class "Default")
      (node (ref "J1") (pin "175") (pinfunction "175_175") (pintype "passive+no_connect"))
    )
    (net (code "200") (name "unconnected-(J1-Pad182)") (class "Default")
      (node (ref "J1") (pin "182") (pinfunction "182_182") (pintype "passive+no_connect"))
    )
    (net (code "201") (name "unconnected-(J1-Pad183)") (class "Default")
      (node (ref "J1") (pin "183") (pinfunction "183_183") (pintype "passive+no_connect"))
    )
    (net (code "202") (name "unconnected-(J1-Pad203)") (class "Default")
      (node (ref "J1") (pin "203") (pinfunction "203_203") (pintype "passive+no_connect"))
    )
    (net (code "203") (name "unconnected-(J1-Pad205)") (class "Default")
      (node (ref "J1") (pin "205") (pinfunction "205_205") (pintype "passive+no_connect"))
    )
    (net (code "204") (name "unconnected-(J1-Pad207)") (class "Default")
      (node (ref "J1") (pin "207") (pinfunction "207_207") (pintype "passive+no_connect"))
    )
    (net (code "205") (name "unconnected-(J1-Pad209)") (class "Default")
      (node (ref "J1") (pin "209") (pinfunction "209_209") (pintype "passive+no_connect"))
    )
    (net (code "206") (name "unconnected-(J1-Pad219)") (class "Default")
      (node (ref "J1") (pin "219") (pinfunction "219_219") (pintype "passive+no_connect"))
    )
    (net (code "207") (name "unconnected-(J1-Pad220)") (class "Default")
      (node (ref "J1") (pin "220") (pinfunction "220_220") (pintype "passive+no_connect"))
    )
    (net (code "208") (name "unconnected-(J1-Pad221)") (class "Default")
      (node (ref "J1") (pin "221") (pinfunction "221_221") (pintype "passive+no_connect"))
    )
    (net (code "209") (name "unconnected-(J1-Pad222)") (class "Default")
      (node (ref "J1") (pin "222") (pinfunction "222_222") (pintype "passive+no_connect"))
    )
    (net (code "210") (name "unconnected-(J1-Pad223)") (class "Default")
      (node (ref "J1") (pin "223") (pinfunction "223_223") (pintype "passive+no_connect"))
    )
    (net (code "211") (name "unconnected-(J1-Pad224)") (class "Default")
      (node (ref "J1") (pin "224") (pinfunction "224_224") (pintype "passive+no_connect"))
    )
    (net (code "212") (name "unconnected-(J1-Pad225)") (class "Default")
      (node (ref "J1") (pin "225") (pinfunction "225_225") (pintype "passive+no_connect"))
    )
    (net (code "213") (name "unconnected-(J1-Pad226)") (class "Default")
      (node (ref "J1") (pin "226") (pinfunction "226_226") (pintype "passive+no_connect"))
    )
    (net (code "214") (name "unconnected-(J1-Pad227)") (class "Default")
      (node (ref "J1") (pin "227") (pinfunction "227_227") (pintype "passive+no_connect"))
    )
    (net (code "215") (name "unconnected-(J1-Pad229)") (class "Default")
      (node (ref "J1") (pin "229") (pinfunction "229_229") (pintype "passive+no_connect"))
    )
    (net (code "216") (name "unconnected-(J1-Pad232)") (class "Default")
      (node (ref "J1") (pin "232") (pinfunction "232_232") (pintype "passive+no_connect"))
    )
    (net (code "217") (name "unconnected-(J1-Pad234)") (class "Default")
      (node (ref "J1") (pin "234") (pinfunction "234_234") (pintype "passive+no_connect"))
    )
    (net (code "218") (name "unconnected-(U11-NC-Pad1)") (class "Default")
      (node (ref "U11") (pin "1") (pinfunction "NC_1") (pintype "passive+no_connect"))
    )
    (net (code "219") (name "unconnected-(U12-NC-Pad1)") (class "Default")
      (node (ref "U12") (pin "1") (pinfunction "NC_1") (pintype "passive+no_connect"))
    )
  )
)
